# AutoPBT.net
KiCad netlist of a schematic drawn in EAGLE
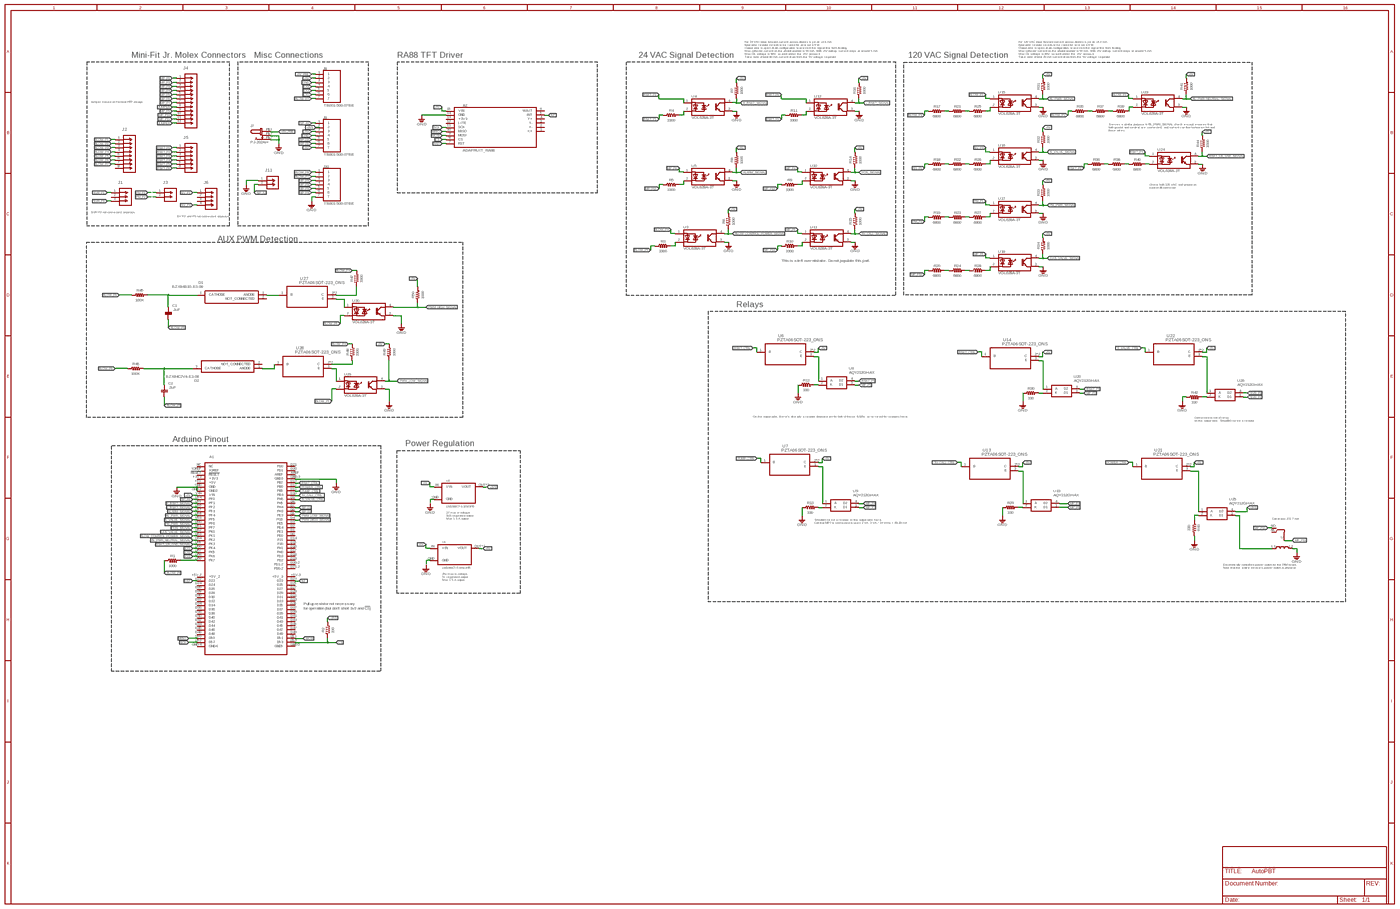
[diagram p0: schematic, sheet 1, overview]
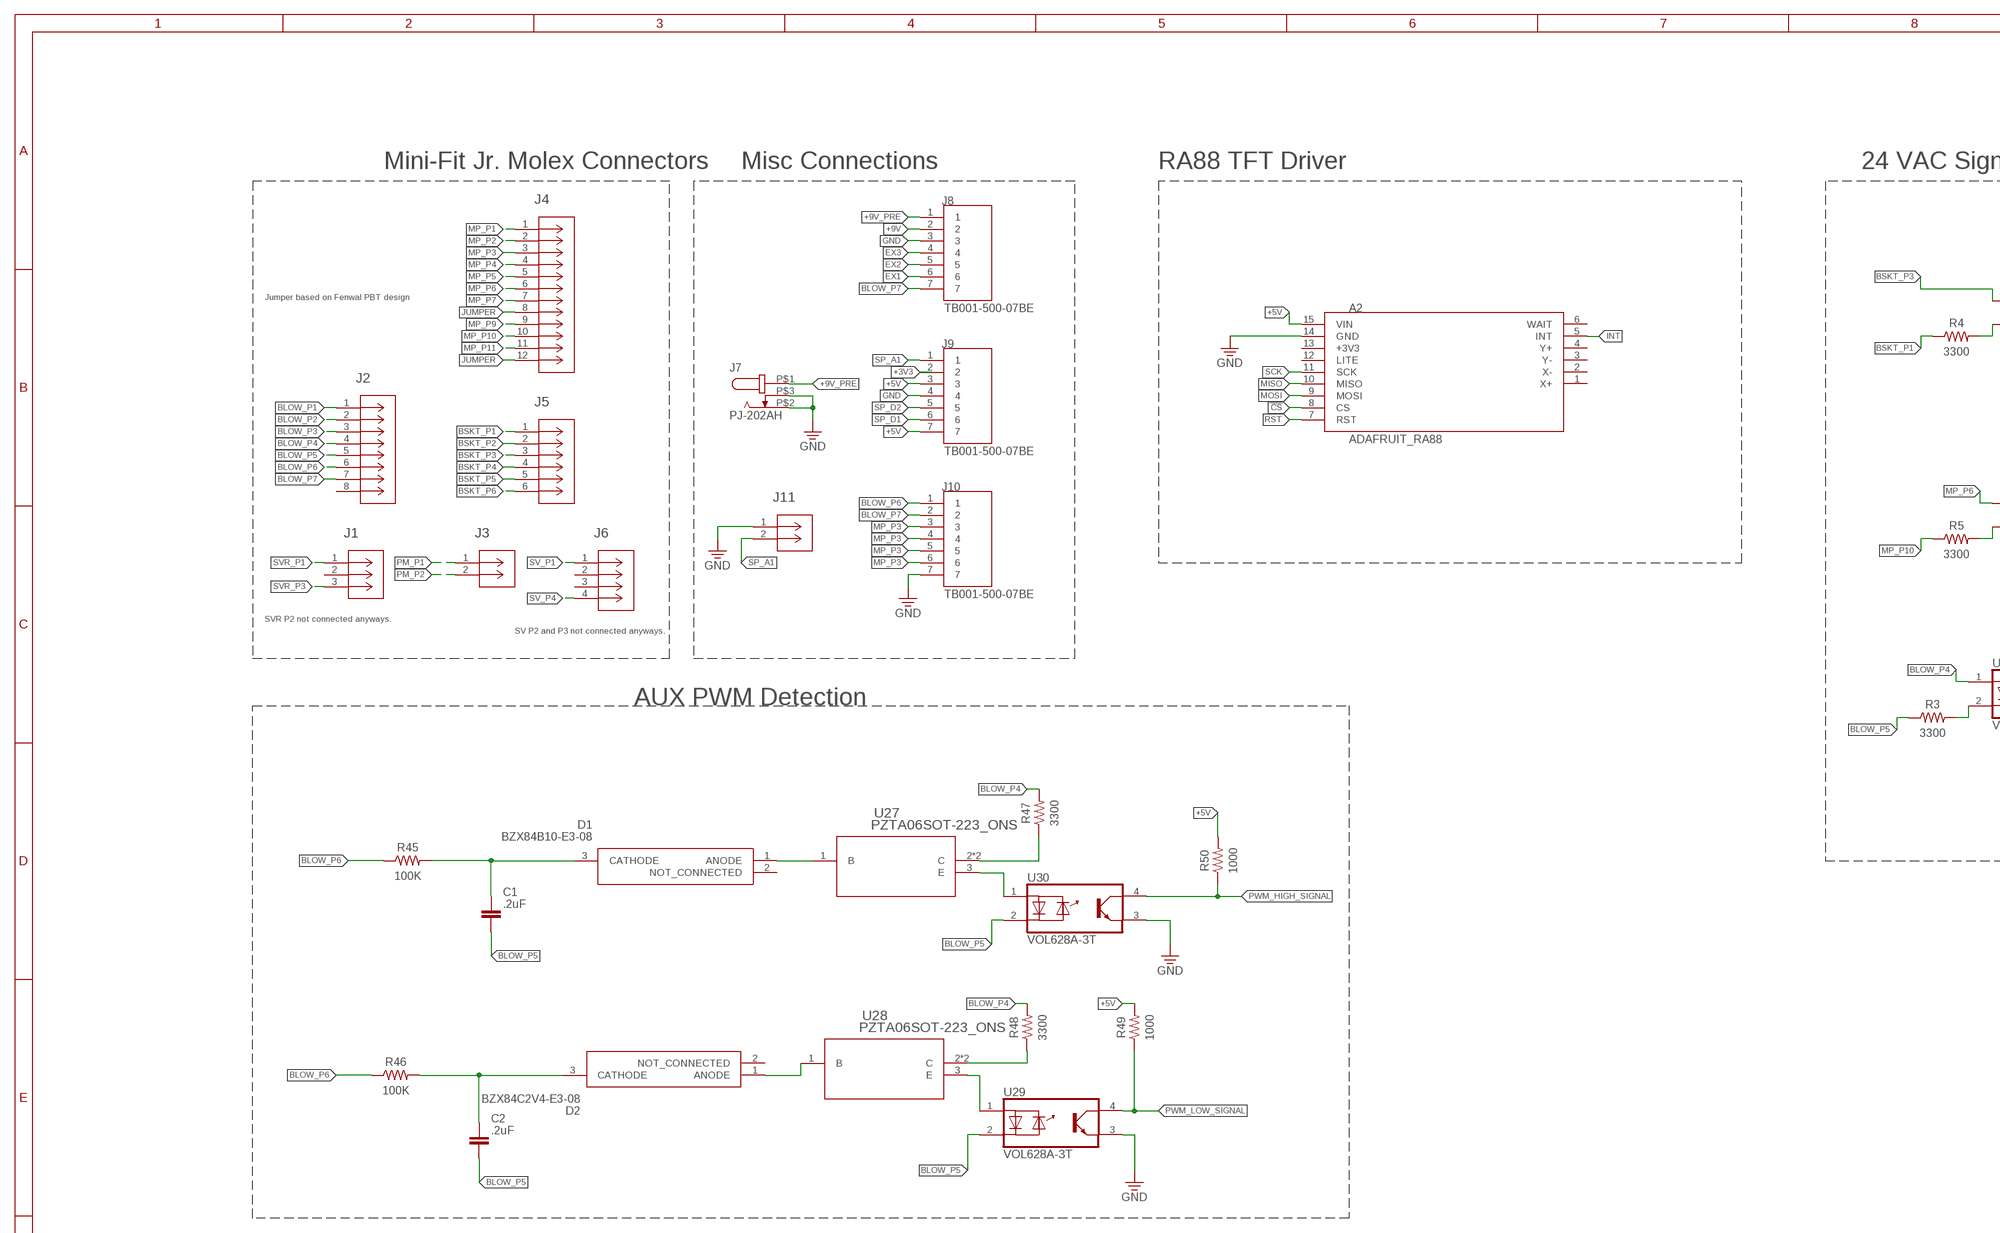
[diagram p1: schematic, sheet 1, part 1 of 4]
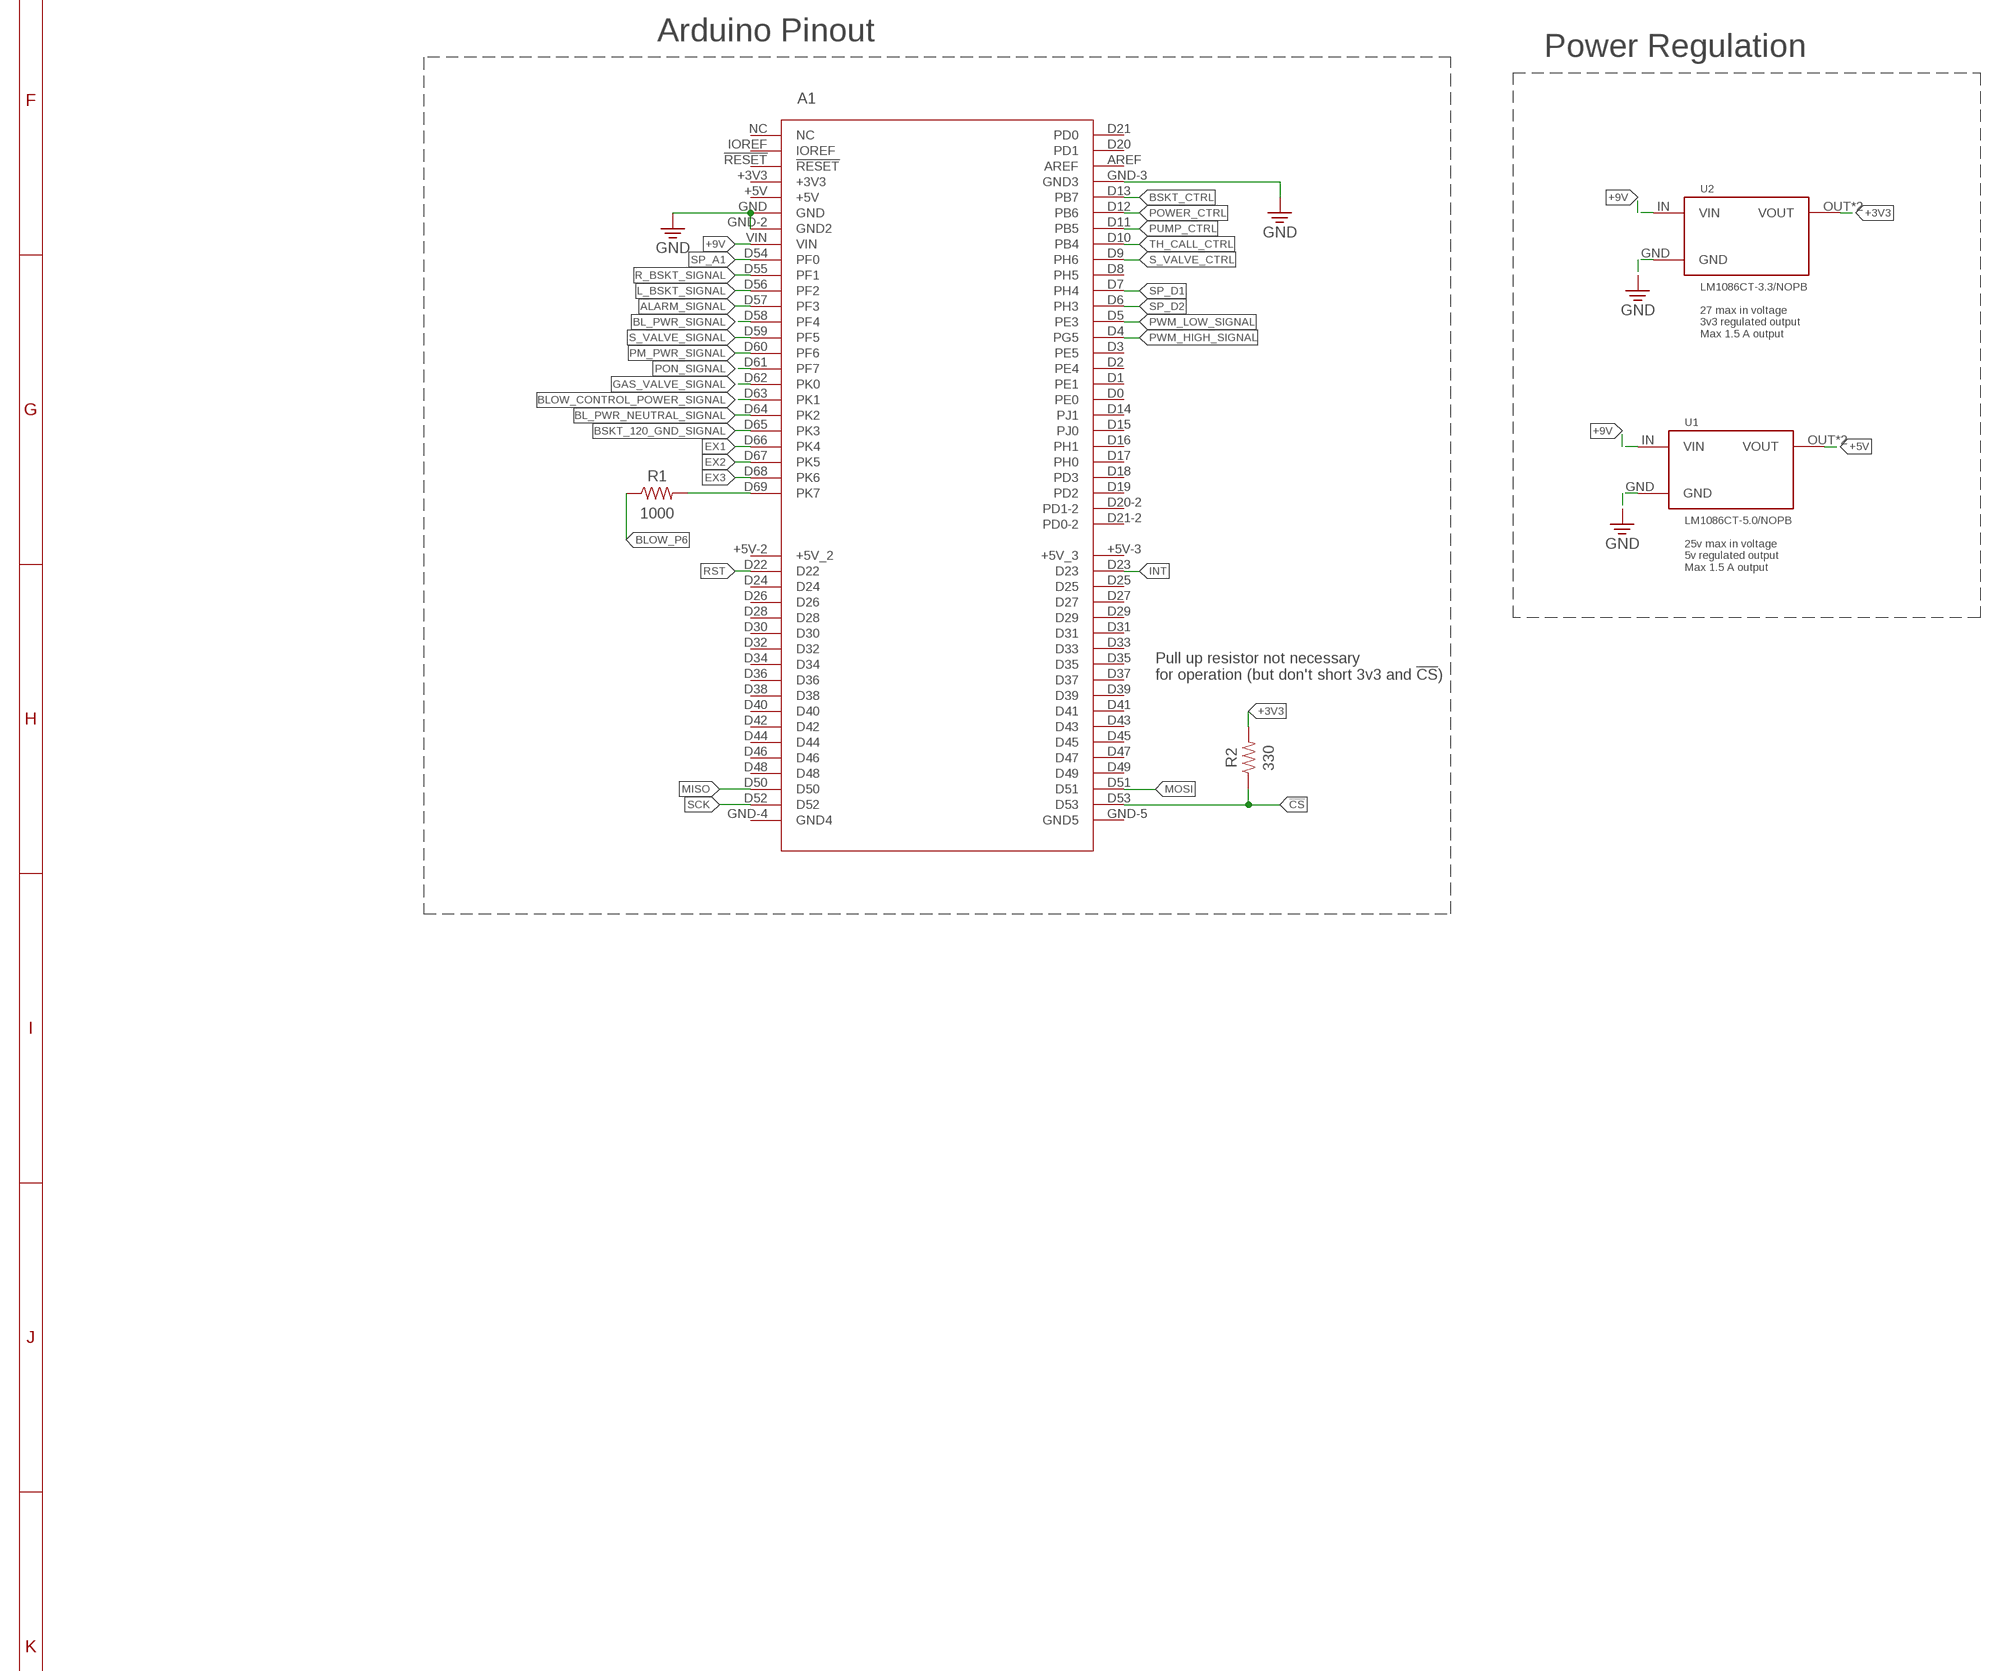
[diagram p2: schematic, sheet 1, part 2 of 4]
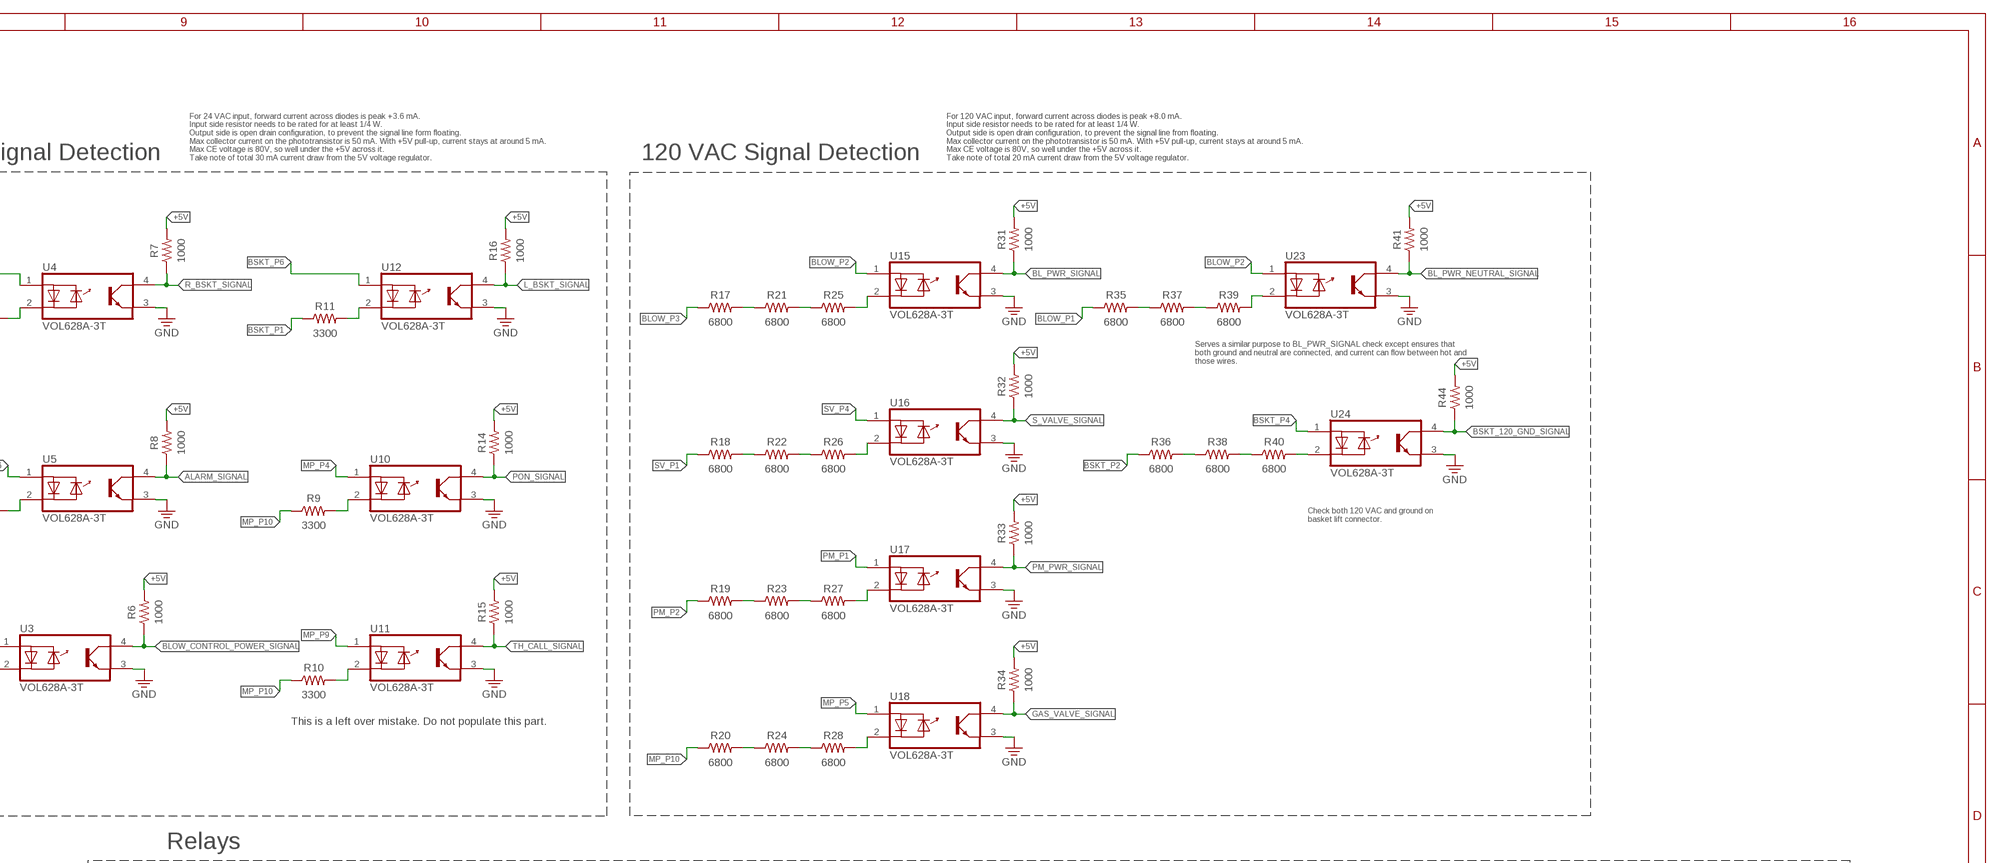
[diagram p3: schematic, sheet 1, part 3 of 4]
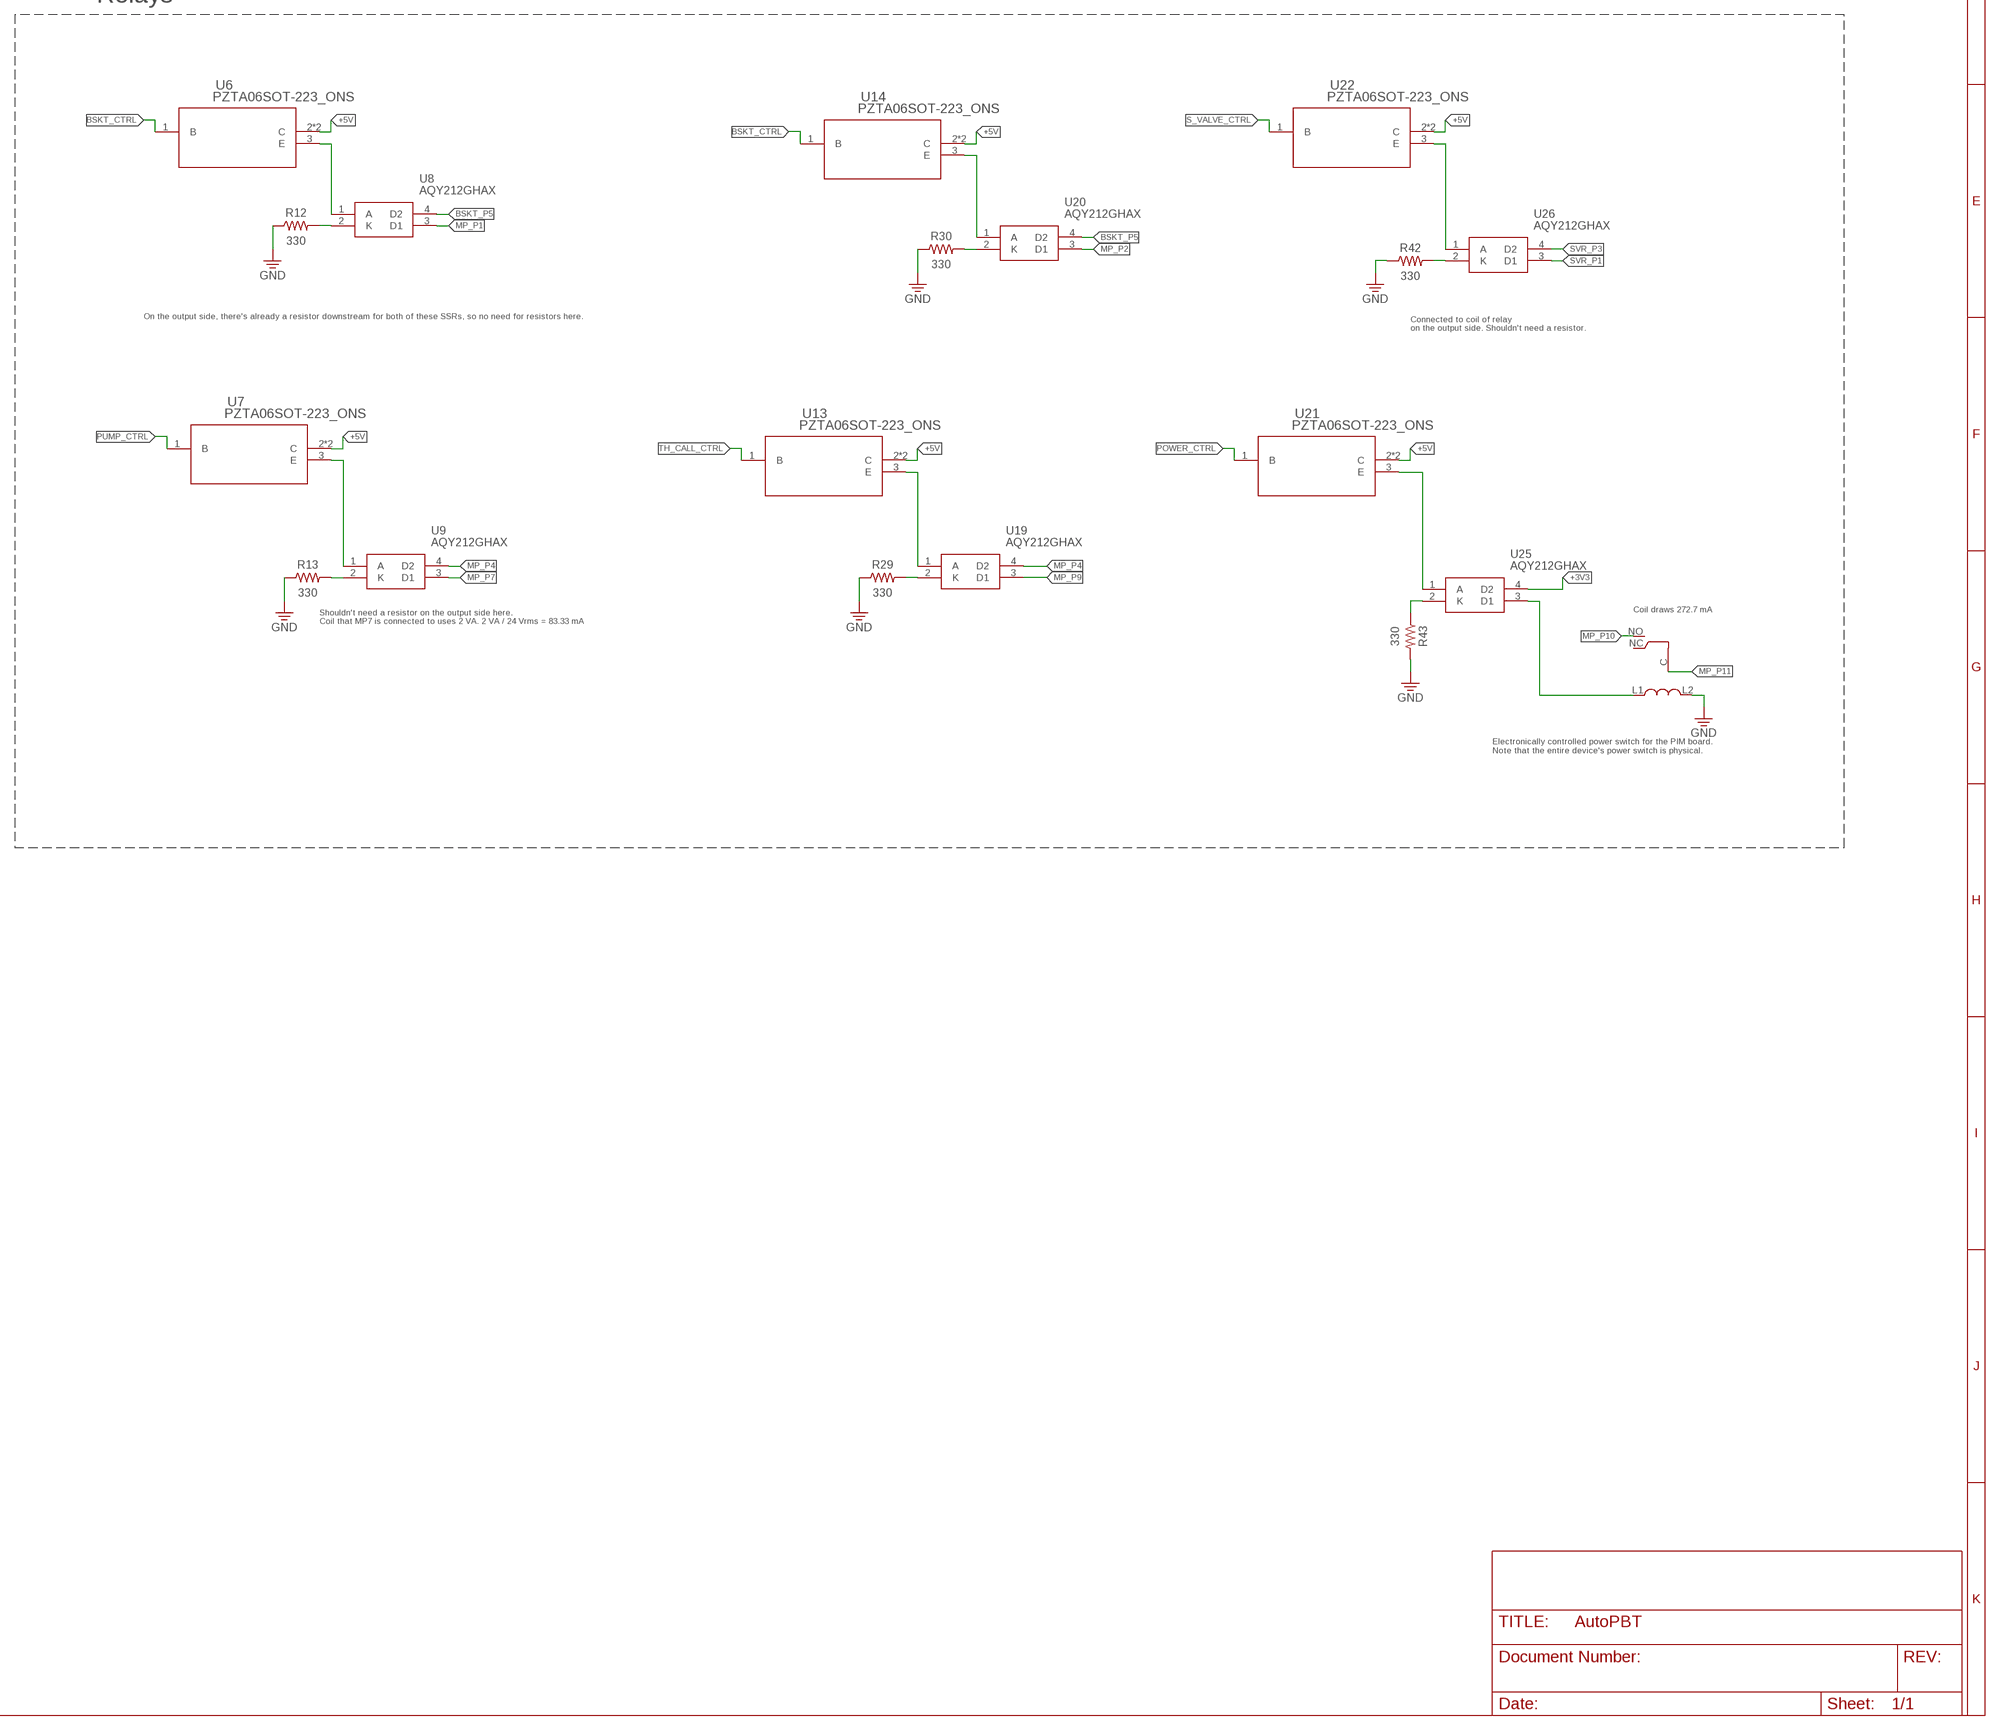
[diagram p4: schematic, sheet 1, part 4 of 4]

(export (version "E")
  (design (tool "Eeschema 10.0.6"))
  (components
    (comp (ref "A1")
      (value "ARDUINO2560ARDUINO2560ACTUAL")
      (footprint "eagle-import:ARDUINO2560PINS")
      (libsource (lib "eagle-import") (part "ARDUINO2560ARDUINO2560ACTUAL"))
    )
    (comp (ref "A2")
      (value "ADAFRUIT_RA88")
      (footprint "eagle-import:RA88")
      (libsource (lib "eagle-import") (part "ADAFRUIT_RA88"))
    )
    (comp (ref "C1")
      (value ".2uF")
      (footprint "eagle-import:CAPC1608X85")
      (libsource (lib "eagle-import") (part "CCHIP-0603(1608-METRIC)_"))
    )
    (comp (ref "C2")
      (value ".2uF")
      (footprint "eagle-import:CAPC1608X85")
      (libsource (lib "eagle-import") (part "CCHIP-0603(1608-METRIC)_"))
    )
    (comp (ref "D1")
      (value "BZX84B10-E3-08")
      (footprint "eagle-import:SOT95P248X115-3N")
      (libsource (lib "eagle-import") (part "BZX84B10-E3-08"))
    )
    (comp (ref "D2")
      (value "BZX84C2V4-E3-08")
      (footprint "eagle-import:SOT95P248X115-3N")
      (fields (field (name "MOUSER_PART_NUMBER") "78-BZX84C2V4-E3-08"))
      (libsource (lib "eagle-import") (part "BZX84C2V4-E3-08"))
    )
    (comp (ref "J1")
      (value "39301039CON_39301039")
      (footprint "eagle-import:CON_39301039")
      (fields
        (field (name "MANUFACTURER_PART_NUMBER") "39301039")
        (field (name "COPYRIGHT") "Copyright (C) 2022 Ultra Librarian. All rights reserved.")
      )
      (libsource (lib "eagle-import") (part "39301039CON_39301039"))
    )
    (comp (ref "J2")
      (value "39281083CON_39281083")
      (footprint "eagle-import:CON_39281083")
      (fields
        (field (name "MANUFACTURER_PART_NUMBER") "39281083")
        (field (name "COPYRIGHT") "Copyright (C) 2022 Ultra Librarian. All rights reserved.")
      )
      (libsource (lib "eagle-import") (part "39281083CON_39281083"))
    )
    (comp (ref "J3")
      (value "39281023CON_39281023")
      (footprint "eagle-import:CON_39281023")
      (fields
        (field (name "MANUFACTURER_PART_NUMBER") "39281023")
        (field (name "COPYRIGHT") "Copyright (C) 2022 Ultra Librarian. All rights reserved.")
      )
      (libsource (lib "eagle-import") (part "39281023CON_39281023"))
    )
    (comp (ref "J4")
      (value "39281123CON_39281123")
      (footprint "eagle-import:CON_39281123")
      (fields
        (field (name "MANUFACTURER_PART_NUMBER") "39281123")
        (field (name "COPYRIGHT") "Copyright (C) 2022 Ultra Librarian. All rights reserved.")
      )
      (libsource (lib "eagle-import") (part "39281123CON_39281123"))
    )
    (comp (ref "J5")
      (value "39281063CON_39281063")
      (footprint "eagle-import:CON_39281063")
      (fields
        (field (name "MANUFACTURER_PART_NUMBER") "39281063")
        (field (name "COPYRIGHT") "Copyright (C) 2022 Ultra Librarian. All rights reserved.")
      )
      (libsource (lib "eagle-import") (part "39281063CON_39281063"))
    )
    (comp (ref "J6")
      (value "39299046CON_39299046")
      (footprint "eagle-import:CON_39299046")
      (fields
        (field (name "MANUFACTURER_PART_NUMBER") "39299046")
        (field (name "COPYRIGHT") "Copyright (C) 2022 Ultra Librarian. All rights reserved.")
      )
      (libsource (lib "eagle-import") (part "39299046CON_39299046"))
    )
    (comp (ref "J7")
      (value "PJ-202AH")
      (footprint "eagle-import:CUI_PJ-202AH")
      (fields (field (name "MANUFACTURER") "CUI INC"))
      (libsource (lib "eagle-import") (part "PJ-202AH"))
    )
    (comp (ref "J8")
      (value "TB001-500-07BE")
      (footprint "eagle-import:CUI_TB001-500-07BE")
      (fields (field (name "MANUFACTURER") "CUI"))
      (libsource (lib "eagle-import") (part "TB001-500-07BE"))
    )
    (comp (ref "J9")
      (value "TB001-500-07BE")
      (footprint "eagle-import:CUI_TB001-500-07BE")
      (fields (field (name "MANUFACTURER") "CUI"))
      (libsource (lib "eagle-import") (part "TB001-500-07BE"))
    )
    (comp (ref "J10")
      (value "TB001-500-07BE")
      (footprint "eagle-import:CUI_TB001-500-07BE")
      (fields (field (name "MANUFACTURER") "CUI"))
      (libsource (lib "eagle-import") (part "TB001-500-07BE"))
    )
    (comp (ref "J11")
      (value "430450212CON_430450212_MOL")
      (footprint "eagle-import:CON_430450212_MOL")
      (fields
        (field (name "MANUFACTURER_PART_NUMBER") "430450212")
        (field (name "COPYRIGHT") "Copyright (C) 2022 Ultra Librarian. All rights reserved.")
      )
      (libsource (lib "eagle-import") (part "430450212CON_430450212_MOL"))
    )
    (comp (ref "K1")
      (value "J107F1CS203VDC.80")
      (footprint "eagle-import:J107F1CS203VDC.80")
      (libsource (lib "eagle-import") (part "J107F1CS203VDC.80"))
    )
    (comp (ref "R1")
      (value "1000")
      (footprint "eagle-import:RESC1608X60")
      (libsource (lib "eagle-import") (part "R-USCHIP-0603(1608-METRIC)_"))
    )
    (comp (ref "R2")
      (value "330")
      (footprint "eagle-import:RESC1608X60")
      (libsource (lib "eagle-import") (part "R-USCHIP-0603(1608-METRIC)_"))
    )
    (comp (ref "R3")
      (value "3300")
      (footprint "eagle-import:RESC1608X60")
      (libsource (lib "eagle-import") (part "R-USCHIP-0603(1608-METRIC)_"))
    )
    (comp (ref "R4")
      (value "3300")
      (footprint "eagle-import:RESC1608X60")
      (libsource (lib "eagle-import") (part "R-USCHIP-0603(1608-METRIC)_"))
    )
    (comp (ref "R5")
      (value "3300")
      (footprint "eagle-import:RESC1608X60")
      (libsource (lib "eagle-import") (part "R-USCHIP-0603(1608-METRIC)_"))
    )
    (comp (ref "R6")
      (value "1000")
      (footprint "eagle-import:RESC1608X60")
      (libsource (lib "eagle-import") (part "R-USCHIP-0603(1608-METRIC)_"))
    )
    (comp (ref "R7")
      (value "1000")
      (footprint "eagle-import:RESC1608X60")
      (libsource (lib "eagle-import") (part "R-USCHIP-0603(1608-METRIC)_"))
    )
    (comp (ref "R8")
      (value "1000")
      (footprint "eagle-import:RESC1608X60")
      (libsource (lib "eagle-import") (part "R-USCHIP-0603(1608-METRIC)_"))
    )
    (comp (ref "R9")
      (value "3300")
      (footprint "eagle-import:RESC1608X60")
      (libsource (lib "eagle-import") (part "R-USCHIP-0603(1608-METRIC)_"))
    )
    (comp (ref "R10")
      (value "3300")
      (footprint "eagle-import:RESC1608X60")
      (libsource (lib "eagle-import") (part "R-USCHIP-0603(1608-METRIC)_"))
    )
    (comp (ref "R11")
      (value "3300")
      (footprint "eagle-import:RESC1608X60")
      (libsource (lib "eagle-import") (part "R-USCHIP-0603(1608-METRIC)_"))
    )
    (comp (ref "R12")
      (value "330")
      (footprint "eagle-import:RESC1608X60")
      (libsource (lib "eagle-import") (part "R-USCHIP-0603(1608-METRIC)_"))
    )
    (comp (ref "R13")
      (value "330")
      (footprint "eagle-import:RESC1608X60")
      (libsource (lib "eagle-import") (part "R-USCHIP-0603(1608-METRIC)_"))
    )
    (comp (ref "R14")
      (value "1000")
      (footprint "eagle-import:RESC1608X60")
      (libsource (lib "eagle-import") (part "R-USCHIP-0603(1608-METRIC)_"))
    )
    (comp (ref "R15")
      (value "1000")
      (footprint "eagle-import:RESC1608X60")
      (libsource (lib "eagle-import") (part "R-USCHIP-0603(1608-METRIC)_"))
    )
    (comp (ref "R16")
      (value "1000")
      (footprint "eagle-import:RESC1608X60")
      (libsource (lib "eagle-import") (part "R-USCHIP-0603(1608-METRIC)_"))
    )
    (comp (ref "R17")
      (value "6800")
      (footprint "eagle-import:RESC1608X60")
      (libsource (lib "eagle-import") (part "R-USCHIP-0603(1608-METRIC)_"))
    )
    (comp (ref "R18")
      (value "6800")
      (footprint "eagle-import:RESC1608X60")
      (libsource (lib "eagle-import") (part "R-USCHIP-0603(1608-METRIC)_"))
    )
    (comp (ref "R19")
      (value "6800")
      (footprint "eagle-import:RESC1608X60")
      (libsource (lib "eagle-import") (part "R-USCHIP-0603(1608-METRIC)_"))
    )
    (comp (ref "R20")
      (value "6800")
      (footprint "eagle-import:RESC1608X60")
      (libsource (lib "eagle-import") (part "R-USCHIP-0603(1608-METRIC)_"))
    )
    (comp (ref "R21")
      (value "6800")
      (footprint "eagle-import:RESC1608X60")
      (libsource (lib "eagle-import") (part "R-USCHIP-0603(1608-METRIC)_"))
    )
    (comp (ref "R22")
      (value "6800")
      (footprint "eagle-import:RESC1608X60")
      (libsource (lib "eagle-import") (part "R-USCHIP-0603(1608-METRIC)_"))
    )
    (comp (ref "R23")
      (value "6800")
      (footprint "eagle-import:RESC1608X60")
      (libsource (lib "eagle-import") (part "R-USCHIP-0603(1608-METRIC)_"))
    )
    (comp (ref "R24")
      (value "6800")
      (footprint "eagle-import:RESC1608X60")
      (libsource (lib "eagle-import") (part "R-USCHIP-0603(1608-METRIC)_"))
    )
    (comp (ref "R25")
      (value "6800")
      (footprint "eagle-import:RESC1608X60")
      (libsource (lib "eagle-import") (part "R-USCHIP-0603(1608-METRIC)_"))
    )
    (comp (ref "R26")
      (value "6800")
      (footprint "eagle-import:RESC1608X60")
      (libsource (lib "eagle-import") (part "R-USCHIP-0603(1608-METRIC)_"))
    )
    (comp (ref "R27")
      (value "6800")
      (footprint "eagle-import:RESC1608X60")
      (libsource (lib "eagle-import") (part "R-USCHIP-0603(1608-METRIC)_"))
    )
    (comp (ref "R28")
      (value "6800")
      (footprint "eagle-import:RESC1608X60")
      (libsource (lib "eagle-import") (part "R-USCHIP-0603(1608-METRIC)_"))
    )
    (comp (ref "R29")
      (value "330")
      (footprint "eagle-import:RESC1608X60")
      (libsource (lib "eagle-import") (part "R-USCHIP-0603(1608-METRIC)_"))
    )
    (comp (ref "R30")
      (value "330")
      (footprint "eagle-import:RESC1608X60")
      (libsource (lib "eagle-import") (part "R-USCHIP-0603(1608-METRIC)_"))
    )
    (comp (ref "R31")
      (value "1000")
      (footprint "eagle-import:RESC1608X60")
      (libsource (lib "eagle-import") (part "R-USCHIP-0603(1608-METRIC)_"))
    )
    (comp (ref "R32")
      (value "1000")
      (footprint "eagle-import:RESC1608X60")
      (libsource (lib "eagle-import") (part "R-USCHIP-0603(1608-METRIC)_"))
    )
    (comp (ref "R33")
      (value "1000")
      (footprint "eagle-import:RESC1608X60")
      (libsource (lib "eagle-import") (part "R-USCHIP-0603(1608-METRIC)_"))
    )
    (comp (ref "R34")
      (value "1000")
      (footprint "eagle-import:RESC1608X60")
      (libsource (lib "eagle-import") (part "R-USCHIP-0603(1608-METRIC)_"))
    )
    (comp (ref "R35")
      (value "6800")
      (footprint "eagle-import:RESC1608X60")
      (libsource (lib "eagle-import") (part "R-USCHIP-0603(1608-METRIC)_"))
    )
    (comp (ref "R36")
      (value "6800")
      (footprint "eagle-import:RESC1608X60")
      (libsource (lib "eagle-import") (part "R-USCHIP-0603(1608-METRIC)_"))
    )
    (comp (ref "R37")
      (value "6800")
      (footprint "eagle-import:RESC1608X60")
      (libsource (lib "eagle-import") (part "R-USCHIP-0603(1608-METRIC)_"))
    )
    (comp (ref "R38")
      (value "6800")
      (footprint "eagle-import:RESC1608X60")
      (libsource (lib "eagle-import") (part "R-USCHIP-0603(1608-METRIC)_"))
    )
    (comp (ref "R39")
      (value "6800")
      (footprint "eagle-import:RESC1608X60")
      (libsource (lib "eagle-import") (part "R-USCHIP-0603(1608-METRIC)_"))
    )
    (comp (ref "R40")
      (value "6800")
      (footprint "eagle-import:RESC1608X60")
      (libsource (lib "eagle-import") (part "R-USCHIP-0603(1608-METRIC)_"))
    )
    (comp (ref "R41")
      (value "1000")
      (footprint "eagle-import:RESC1608X60")
      (libsource (lib "eagle-import") (part "R-USCHIP-0603(1608-METRIC)_"))
    )
    (comp (ref "R42")
      (value "330")
      (footprint "eagle-import:RESC1608X60")
      (libsource (lib "eagle-import") (part "R-USCHIP-0603(1608-METRIC)_"))
    )
    (comp (ref "R43")
      (value "330")
      (footprint "eagle-import:RESC1608X60")
      (libsource (lib "eagle-import") (part "R-USCHIP-0603(1608-METRIC)_"))
    )
    (comp (ref "R44")
      (value "1000")
      (footprint "eagle-import:RESC1608X60")
      (libsource (lib "eagle-import") (part "R-USCHIP-0603(1608-METRIC)_"))
    )
    (comp (ref "R45")
      (value "100K")
      (footprint "eagle-import:RESC1608X60")
      (libsource (lib "eagle-import") (part "R-USCHIP-0603(1608-METRIC)_"))
    )
    (comp (ref "R46")
      (value "100K")
      (footprint "eagle-import:RESC1608X60")
      (libsource (lib "eagle-import") (part "R-USCHIP-0603(1608-METRIC)_"))
    )
    (comp (ref "R47")
      (value "3300")
      (footprint "eagle-import:RESC1608X60")
      (libsource (lib "eagle-import") (part "R-USCHIP-0603(1608-METRIC)_"))
    )
    (comp (ref "R48")
      (value "3300")
      (footprint "eagle-import:RESC1608X60")
      (libsource (lib "eagle-import") (part "R-USCHIP-0603(1608-METRIC)_"))
    )
    (comp (ref "R49")
      (value "1000")
      (footprint "eagle-import:RESC1608X60")
      (libsource (lib "eagle-import") (part "R-USCHIP-0603(1608-METRIC)_"))
    )
    (comp (ref "R50")
      (value "1000")
      (footprint "eagle-import:RESC1608X60")
      (libsource (lib "eagle-import") (part "R-USCHIP-0603(1608-METRIC)_"))
    )
    (comp (ref "U1")
      (value "LM1086CT-5.0/NOPB")
      (footprint "eagle-import:LM1086CT-3.3_NOPB")
      (libsource (lib "eagle-import") (part "LM1086CT-5.0/NOPB"))
    )
    (comp (ref "U2")
      (value "LM1086CT-3.3/NOPB")
      (footprint "eagle-import:LM1086CT-3.3_NOPB")
      (libsource (lib "eagle-import") (part "LM1086CT-3.3/NOPB"))
    )
    (comp (ref "U3")
      (value "VOL628A-3T")
      (footprint "eagle-import:SOIC254P1020X230-4N")
      (fields (field (name "MANUFACTURER") "VISHAY"))
      (libsource (lib "eagle-import") (part "VOL628A-3T"))
    )
    (comp (ref "U4")
      (value "VOL628A-3T")
      (footprint "eagle-import:SOIC254P1020X230-4N")
      (fields (field (name "MANUFACTURER") "VISHAY"))
      (libsource (lib "eagle-import") (part "VOL628A-3T"))
    )
    (comp (ref "U5")
      (value "VOL628A-3T")
      (footprint "eagle-import:SOIC254P1020X230-4N")
      (fields (field (name "MANUFACTURER") "VISHAY"))
      (libsource (lib "eagle-import") (part "VOL628A-3T"))
    )
    (comp (ref "U6")
      (value "PZTA06SOT-223_ONS")
      (footprint "eagle-import:SOT-223_ONS")
      (fields
        (field (name "MANUFACTURER_PART_NUMBER") "PZTA06")
        (field (name "COPYRIGHT") "Copyright (C) 2022 Ultra Librarian. All rights reserved.")
      )
      (libsource (lib "eagle-import") (part "PZTA06SOT-223_ONS"))
    )
    (comp (ref "U7")
      (value "PZTA06SOT-223_ONS")
      (footprint "eagle-import:SOT-223_ONS")
      (fields
        (field (name "MANUFACTURER_PART_NUMBER") "PZTA06")
        (field (name "COPYRIGHT") "Copyright (C) 2022 Ultra Librarian. All rights reserved.")
      )
      (libsource (lib "eagle-import") (part "PZTA06SOT-223_ONS"))
    )
    (comp (ref "U8")
      (value "AQY212GHAX")
      (footprint "eagle-import:SOP254P962X315-4N")
      (fields (field (name "MOUSER_PART_NUMBER") "667-AQY212GHAX"))
      (libsource (lib "eagle-import") (part "AQY212GHAX"))
    )
    (comp (ref "U9")
      (value "AQY212GHAX")
      (footprint "eagle-import:SOP254P962X315-4N")
      (fields (field (name "MOUSER_PART_NUMBER") "667-AQY212GHAX"))
      (libsource (lib "eagle-import") (part "AQY212GHAX"))
    )
    (comp (ref "U10")
      (value "VOL628A-3T")
      (footprint "eagle-import:SOIC254P1020X230-4N")
      (fields (field (name "MANUFACTURER") "VISHAY"))
      (libsource (lib "eagle-import") (part "VOL628A-3T"))
    )
    (comp (ref "U11")
      (value "VOL628A-3T")
      (footprint "eagle-import:SOIC254P1020X230-4N")
      (fields (field (name "MANUFACTURER") "VISHAY"))
      (libsource (lib "eagle-import") (part "VOL628A-3T"))
    )
    (comp (ref "U12")
      (value "VOL628A-3T")
      (footprint "eagle-import:SOIC254P1020X230-4N")
      (fields (field (name "MANUFACTURER") "VISHAY"))
      (libsource (lib "eagle-import") (part "VOL628A-3T"))
    )
    (comp (ref "U13")
      (value "PZTA06SOT-223_ONS")
      (footprint "eagle-import:SOT-223_ONS")
      (fields
        (field (name "MANUFACTURER_PART_NUMBER") "PZTA06")
        (field (name "COPYRIGHT") "Copyright (C) 2022 Ultra Librarian. All rights reserved.")
      )
      (libsource (lib "eagle-import") (part "PZTA06SOT-223_ONS"))
    )
    (comp (ref "U14")
      (value "PZTA06SOT-223_ONS")
      (footprint "eagle-import:SOT-223_ONS")
      (fields
        (field (name "MANUFACTURER_PART_NUMBER") "PZTA06")
        (field (name "COPYRIGHT") "Copyright (C) 2022 Ultra Librarian. All rights reserved.")
      )
      (libsource (lib "eagle-import") (part "PZTA06SOT-223_ONS"))
    )
    (comp (ref "U15")
      (value "VOL628A-3T")
      (footprint "eagle-import:SOIC254P1020X230-4N")
      (fields (field (name "MANUFACTURER") "VISHAY"))
      (libsource (lib "eagle-import") (part "VOL628A-3T"))
    )
    (comp (ref "U16")
      (value "VOL628A-3T")
      (footprint "eagle-import:SOIC254P1020X230-4N")
      (fields (field (name "MANUFACTURER") "VISHAY"))
      (libsource (lib "eagle-import") (part "VOL628A-3T"))
    )
    (comp (ref "U17")
      (value "VOL628A-3T")
      (footprint "eagle-import:SOIC254P1020X230-4N")
      (fields (field (name "MANUFACTURER") "VISHAY"))
      (libsource (lib "eagle-import") (part "VOL628A-3T"))
    )
    (comp (ref "U18")
      (value "VOL628A-3T")
      (footprint "eagle-import:SOIC254P1020X230-4N")
      (fields (field (name "MANUFACTURER") "VISHAY"))
      (libsource (lib "eagle-import") (part "VOL628A-3T"))
    )
    (comp (ref "U19")
      (value "AQY212GHAX")
      (footprint "eagle-import:SOP254P962X315-4N")
      (fields (field (name "MOUSER_PART_NUMBER") "667-AQY212GHAX"))
      (libsource (lib "eagle-import") (part "AQY212GHAX"))
    )
    (comp (ref "U20")
      (value "AQY212GHAX")
      (footprint "eagle-import:SOP254P962X315-4N")
      (fields (field (name "MOUSER_PART_NUMBER") "667-AQY212GHAX"))
      (libsource (lib "eagle-import") (part "AQY212GHAX"))
    )
    (comp (ref "U21")
      (value "PZTA06SOT-223_ONS")
      (footprint "eagle-import:SOT-223_ONS")
      (fields
        (field (name "MANUFACTURER_PART_NUMBER") "PZTA06")
        (field (name "COPYRIGHT") "Copyright (C) 2022 Ultra Librarian. All rights reserved.")
      )
      (libsource (lib "eagle-import") (part "PZTA06SOT-223_ONS"))
    )
    (comp (ref "U22")
      (value "PZTA06SOT-223_ONS")
      (footprint "eagle-import:SOT-223_ONS")
      (fields
        (field (name "MANUFACTURER_PART_NUMBER") "PZTA06")
        (field (name "COPYRIGHT") "Copyright (C) 2022 Ultra Librarian. All rights reserved.")
      )
      (libsource (lib "eagle-import") (part "PZTA06SOT-223_ONS"))
    )
    (comp (ref "U23")
      (value "VOL628A-3T")
      (footprint "eagle-import:SOIC254P1020X230-4N")
      (fields (field (name "MANUFACTURER") "VISHAY"))
      (libsource (lib "eagle-import") (part "VOL628A-3T"))
    )
    (comp (ref "U24")
      (value "VOL628A-3T")
      (footprint "eagle-import:SOIC254P1020X230-4N")
      (fields (field (name "MANUFACTURER") "VISHAY"))
      (libsource (lib "eagle-import") (part "VOL628A-3T"))
    )
    (comp (ref "U25")
      (value "AQY212GHAX")
      (footprint "eagle-import:SOP254P962X315-4N")
      (fields (field (name "MOUSER_PART_NUMBER") "667-AQY212GHAX"))
      (libsource (lib "eagle-import") (part "AQY212GHAX"))
    )
    (comp (ref "U26")
      (value "AQY212GHAX")
      (footprint "eagle-import:SOP254P962X315-4N")
      (fields (field (name "MOUSER_PART_NUMBER") "667-AQY212GHAX"))
      (libsource (lib "eagle-import") (part "AQY212GHAX"))
    )
    (comp (ref "U27")
      (value "PZTA06SOT-223_ONS")
      (footprint "eagle-import:SOT-223_ONS")
      (fields
        (field (name "MANUFACTURER_PART_NUMBER") "PZTA06")
        (field (name "COPYRIGHT") "Copyright (C) 2022 Ultra Librarian. All rights reserved.")
      )
      (libsource (lib "eagle-import") (part "PZTA06SOT-223_ONS"))
    )
    (comp (ref "U28")
      (value "PZTA06SOT-223_ONS")
      (footprint "eagle-import:SOT-223_ONS")
      (fields
        (field (name "MANUFACTURER_PART_NUMBER") "PZTA06")
        (field (name "COPYRIGHT") "Copyright (C) 2022 Ultra Librarian. All rights reserved.")
      )
      (libsource (lib "eagle-import") (part "PZTA06SOT-223_ONS"))
    )
    (comp (ref "U29")
      (value "VOL628A-3T")
      (footprint "eagle-import:SOIC254P1020X230-4N")
      (fields (field (name "MANUFACTURER") "VISHAY"))
      (libsource (lib "eagle-import") (part "VOL628A-3T"))
    )
    (comp (ref "U30")
      (value "VOL628A-3T")
      (footprint "eagle-import:SOIC254P1020X230-4N")
      (fields (field (name "MANUFACTURER") "VISHAY"))
      (libsource (lib "eagle-import") (part "VOL628A-3T"))
    )
  )
  (nets
    (net (code "1") (name "+3V3") (class "Default")
      (node (ref "J9") (pin "2") (pinfunction "2_2") (pintype "passive"))
      (node (ref "R2") (pin "2") (pinfunction "2_2") (pintype "passive"))
      (node (ref "U2") (pin "OUT") (pinfunction "VOUT_OUT") (pintype "bidirectional"))
      (node (ref "U2") (pin "OUT2") (pinfunction "VOUT_OUT2") (pintype "bidirectional"))
      (node (ref "U25") (pin "4") (pinfunction "D2_4") (pintype "bidirectional"))
    )
    (net (code "2") (name "+5V") (class "Default")
      (node (ref "A2") (pin "15") (pinfunction "VIN_15") (pintype "bidirectional"))
      (node (ref "J9") (pin "3") (pinfunction "3_3") (pintype "passive"))
      (node (ref "J9") (pin "7") (pinfunction "7_7") (pintype "passive"))
      (node (ref "R14") (pin "2") (pinfunction "2_2") (pintype "passive"))
      (node (ref "R15") (pin "2") (pinfunction "2_2") (pintype "passive"))
      (node (ref "R16") (pin "2") (pinfunction "2_2") (pintype "passive"))
      (node (ref "R31") (pin "2") (pinfunction "2_2") (pintype "passive"))
      (node (ref "R32") (pin "2") (pinfunction "2_2") (pintype "passive"))
      (node (ref "R33") (pin "2") (pinfunction "2_2") (pintype "passive"))
      (node (ref "R34") (pin "2") (pinfunction "2_2") (pintype "passive"))
      (node (ref "R41") (pin "2") (pinfunction "2_2") (pintype "passive"))
      (node (ref "R44") (pin "2") (pinfunction "2_2") (pintype "passive"))
      (node (ref "R49") (pin "2") (pinfunction "2_2") (pintype "passive"))
      (node (ref "R50") (pin "2") (pinfunction "2_2") (pintype "passive"))
      (node (ref "R6") (pin "2") (pinfunction "2_2") (pintype "passive"))
      (node (ref "R7") (pin "2") (pinfunction "2_2") (pintype "passive"))
      (node (ref "R8") (pin "2") (pinfunction "2_2") (pintype "passive"))
      (node (ref "U1") (pin "OUT") (pinfunction "VOUT_OUT") (pintype "bidirectional"))
      (node (ref "U1") (pin "OUT2") (pinfunction "VOUT_OUT2") (pintype "bidirectional"))
      (node (ref "U13") (pin "2") (pinfunction "C_2") (pintype "passive"))
      (node (ref "U13") (pin "4") (pinfunction "C_4") (pintype "passive"))
      (node (ref "U14") (pin "2") (pinfunction "C_2") (pintype "passive"))
      (node (ref "U14") (pin "4") (pinfunction "C_4") (pintype "passive"))
      (node (ref "U21") (pin "2") (pinfunction "C_2") (pintype "passive"))
      (node (ref "U21") (pin "4") (pinfunction "C_4") (pintype "passive"))
      (node (ref "U22") (pin "2") (pinfunction "C_2") (pintype "passive"))
      (node (ref "U22") (pin "4") (pinfunction "C_4") (pintype "passive"))
      (node (ref "U6") (pin "2") (pinfunction "C_2") (pintype "passive"))
      (node (ref "U6") (pin "4") (pinfunction "C_4") (pintype "passive"))
      (node (ref "U7") (pin "2") (pinfunction "C_2") (pintype "passive"))
      (node (ref "U7") (pin "4") (pinfunction "C_4") (pintype "passive"))
    )
    (net (code "3") (name "+9V") (class "Default")
      (node (ref "A1") (pin "VIN") (pinfunction "VIN_VIN") (pintype "bidirectional"))
      (node (ref "J8") (pin "2") (pinfunction "2_2") (pintype "passive"))
      (node (ref "U1") (pin "IN") (pinfunction "VIN_IN") (pintype "bidirectional"))
      (node (ref "U2") (pin "IN") (pinfunction "VIN_IN") (pintype "bidirectional"))
    )
    (net (code "4") (name "+9V_PRE") (class "Default")
      (node (ref "J7") (pin "P$1") (pinfunction "1_P$1") (pintype "passive"))
      (node (ref "J8") (pin "1") (pinfunction "1_1") (pintype "passive"))
    )
    (net (code "5") (name "/~{CS}") (class "Default")
      (node (ref "A1") (pin "D53") (pinfunction "D53_D53") (pintype "bidirectional"))
      (node (ref "A2") (pin "8") (pinfunction "CS_8") (pintype "bidirectional"))
      (node (ref "R2") (pin "1") (pinfunction "1_1") (pintype "passive"))
    )
    (net (code "6") (name "ALARM_SIGNAL") (class "Default")
      (node (ref "A1") (pin "D57") (pinfunction "PF3_D57") (pintype "bidirectional"))
      (node (ref "R8") (pin "1") (pinfunction "1_1") (pintype "passive"))
      (node (ref "U5") (pin "4") (pinfunction "CO_4") (pintype "passive"))
    )
    (net (code "7") (name "BLOW_CONTROL_POWER_SIGNAL") (class "Default")
      (node (ref "A1") (pin "D63") (pinfunction "PK1_D63") (pintype "bidirectional"))
      (node (ref "R6") (pin "1") (pinfunction "1_1") (pintype "passive"))
      (node (ref "U3") (pin "4") (pinfunction "CO_4") (pintype "passive"))
    )
    (net (code "8") (name "BLOW_P1") (class "Default")
      (node (ref "J2") (pin "1") (pinfunction "1_1") (pintype "passive"))
      (node (ref "R35") (pin "1") (pinfunction "1_1") (pintype "passive"))
    )
    (net (code "9") (name "BLOW_P2") (class "Default")
      (node (ref "J2") (pin "2") (pinfunction "2_2") (pintype "passive"))
      (node (ref "U15") (pin "1") (pinfunction "A/C_1") (pintype "passive"))
      (node (ref "U23") (pin "1") (pinfunction "A/C_1") (pintype "passive"))
    )
    (net (code "10") (name "BLOW_P3") (class "Default")
      (node (ref "J2") (pin "3") (pinfunction "3_3") (pintype "passive"))
      (node (ref "R17") (pin "1") (pinfunction "1_1") (pintype "passive"))
    )
    (net (code "11") (name "BLOW_P4") (class "Default")
      (node (ref "J2") (pin "4") (pinfunction "4_4") (pintype "passive"))
      (node (ref "R47") (pin "2") (pinfunction "2_2") (pintype "passive"))
      (node (ref "R48") (pin "2") (pinfunction "2_2") (pintype "passive"))
      (node (ref "U3") (pin "1") (pinfunction "A/C_1") (pintype "passive"))
    )
    (net (code "12") (name "BLOW_P5") (class "Default")
      (node (ref "C1") (pin "2") (pinfunction "2_2") (pintype "passive"))
      (node (ref "C2") (pin "2") (pinfunction "2_2") (pintype "passive"))
      (node (ref "J2") (pin "5") (pinfunction "5_5") (pintype "passive"))
      (node (ref "R3") (pin "1") (pinfunction "1_1") (pintype "passive"))
      (node (ref "U29") (pin "2") (pinfunction "C/A_2") (pintype "passive"))
      (node (ref "U30") (pin "2") (pinfunction "C/A_2") (pintype "passive"))
    )
    (net (code "13") (name "BLOW_P6") (class "Default")
      (node (ref "J10") (pin "1") (pinfunction "1_1") (pintype "passive"))
      (node (ref "J2") (pin "6") (pinfunction "6_6") (pintype "passive"))
      (node (ref "R1") (pin "1") (pinfunction "1_1") (pintype "passive"))
      (node (ref "R45") (pin "1") (pinfunction "1_1") (pintype "passive"))
      (node (ref "R46") (pin "1") (pinfunction "1_1") (pintype "passive"))
    )
    (net (code "14") (name "BLOW_P7") (class "Default")
      (node (ref "J10") (pin "2") (pinfunction "2_2") (pintype "passive"))
      (node (ref "J2") (pin "7") (pinfunction "7_7") (pintype "passive"))
      (node (ref "J8") (pin "7") (pinfunction "7_7") (pintype "passive"))
    )
    (net (code "15") (name "BL_PWR_NEUTRAL_SIGNAL") (class "Default")
      (node (ref "A1") (pin "D64") (pinfunction "PK2_D64") (pintype "bidirectional"))
      (node (ref "R41") (pin "1") (pinfunction "1_1") (pintype "passive"))
      (node (ref "U23") (pin "4") (pinfunction "CO_4") (pintype "passive"))
    )
    (net (code "16") (name "BL_PWR_SIGNAL") (class "Default")
      (node (ref "A1") (pin "D58") (pinfunction "PF4_D58") (pintype "bidirectional"))
      (node (ref "R31") (pin "1") (pinfunction "1_1") (pintype "passive"))
      (node (ref "U15") (pin "4") (pinfunction "CO_4") (pintype "passive"))
    )
    (net (code "17") (name "BSKT_120_GND_SIGNAL") (class "Default")
      (node (ref "A1") (pin "D65") (pinfunction "PK3_D65") (pintype "bidirectional"))
      (node (ref "R44") (pin "1") (pinfunction "1_1") (pintype "passive"))
      (node (ref "U24") (pin "4") (pinfunction "CO_4") (pintype "passive"))
    )
    (net (code "18") (name "BSKT_CTRL") (class "Default")
      (node (ref "A1") (pin "D13") (pinfunction "PB7_D13") (pintype "bidirectional"))
      (node (ref "U14") (pin "1") (pinfunction "B_1") (pintype "passive"))
      (node (ref "U6") (pin "1") (pinfunction "B_1") (pintype "passive"))
    )
    (net (code "19") (name "BSKT_P1") (class "Default")
      (node (ref "J5") (pin "1") (pinfunction "1_1") (pintype "passive"))
      (node (ref "R11") (pin "1") (pinfunction "1_1") (pintype "passive"))
      (node (ref "R4") (pin "1") (pinfunction "1_1") (pintype "passive"))
    )
    (net (code "20") (name "BSKT_P2") (class "Default")
      (node (ref "J5") (pin "2") (pinfunction "2_2") (pintype "passive"))
      (node (ref "R36") (pin "1") (pinfunction "1_1") (pintype "passive"))
    )
    (net (code "21") (name "BSKT_P3") (class "Default")
      (node (ref "J5") (pin "3") (pinfunction "3_3") (pintype "passive"))
      (node (ref "U4") (pin "1") (pinfunction "A/C_1") (pintype "passive"))
    )
    (net (code "22") (name "BSKT_P4") (class "Default")
      (node (ref "J5") (pin "4") (pinfunction "4_4") (pintype "passive"))
      (node (ref "U24") (pin "1") (pinfunction "A/C_1") (pintype "passive"))
    )
    (net (code "23") (name "BSKT_P5") (class "Default")
      (node (ref "J5") (pin "5") (pinfunction "5_5") (pintype "passive"))
      (node (ref "U20") (pin "4") (pinfunction "D2_4") (pintype "bidirectional"))
      (node (ref "U8") (pin "4") (pinfunction "D2_4") (pintype "bidirectional"))
    )
    (net (code "24") (name "BSKT_P6") (class "Default")
      (node (ref "J5") (pin "6") (pinfunction "6_6") (pintype "passive"))
      (node (ref "U12") (pin "1") (pinfunction "A/C_1") (pintype "passive"))
    )
    (net (code "25") (name "EX1") (class "Default")
      (node (ref "A1") (pin "D66") (pinfunction "PK4_D66") (pintype "bidirectional"))
      (node (ref "J8") (pin "6") (pinfunction "6_6") (pintype "passive"))
    )
    (net (code "26") (name "EX2") (class "Default")
      (node (ref "A1") (pin "D67") (pinfunction "PK5_D67") (pintype "bidirectional"))
      (node (ref "J8") (pin "5") (pinfunction "5_5") (pintype "passive"))
    )
    (net (code "27") (name "EX3") (class "Default")
      (node (ref "A1") (pin "D68") (pinfunction "PK6_D68") (pintype "bidirectional"))
      (node (ref "J8") (pin "4") (pinfunction "4_4") (pintype "passive"))
    )
    (net (code "28") (name "GAS_VALVE_SIGNAL") (class "Default")
      (node (ref "A1") (pin "D62") (pinfunction "PK0_D62") (pintype "bidirectional"))
      (node (ref "R34") (pin "1") (pinfunction "1_1") (pintype "passive"))
      (node (ref "U18") (pin "4") (pinfunction "CO_4") (pintype "passive"))
    )
    (net (code "29") (name "GND") (class "Default")
      (node (ref "A1") (pin "GND") (pinfunction "GND_GND") (pintype "bidirectional"))
      (node (ref "A1") (pin "GND-2") (pinfunction "GND2_GND-2") (pintype "bidirectional"))
      (node (ref "A1") (pin "GND-3") (pinfunction "GND3_GND-3") (pintype "bidirectional"))
      (node (ref "A2") (pin "14") (pinfunction "GND_14") (pintype "bidirectional"))
      (node (ref "J10") (pin "7") (pinfunction "7_7") (pintype "passive"))
      (node (ref "J11") (pin "1") (pinfunction "1_1") (pintype "passive"))
      (node (ref "J7") (pin "P$2") (pinfunction "2_P$2") (pintype "passive"))
      (node (ref "J7") (pin "P$3") (pinfunction "3_P$3") (pintype "passive"))
      (node (ref "J8") (pin "3") (pinfunction "3_3") (pintype "passive"))
      (node (ref "J9") (pin "4") (pinfunction "4_4") (pintype "passive"))
      (node (ref "K1") (pin "L2") (pinfunction "5_L2") (pintype "bidirectional"))
      (node (ref "R12") (pin "1") (pinfunction "1_1") (pintype "passive"))
      (node (ref "R13") (pin "1") (pinfunction "1_1") (pintype "passive"))
      (node (ref "R29") (pin "1") (pinfunction "1_1") (pintype "passive"))
      (node (ref "R30") (pin "1") (pinfunction "1_1") (pintype "passive"))
      (node (ref "R42") (pin "1") (pinfunction "1_1") (pintype "passive"))
      (node (ref "R43") (pin "2") (pinfunction "2_2") (pintype "passive"))
      (node (ref "U1") (pin "GND") (pinfunction "GND_GND") (pintype "bidirectional"))
      (node (ref "U10") (pin "3") (pinfunction "E_3") (pintype "passive"))
      (node (ref "U11") (pin "3") (pinfunction "E_3") (pintype "passive"))
      (node (ref "U12") (pin "3") (pinfunction "E_3") (pintype "passive"))
      (node (ref "U15") (pin "3") (pinfunction "E_3") (pintype "passive"))
      (node (ref "U16") (pin "3") (pinfunction "E_3") (pintype "passive"))
      (node (ref "U17") (pin "3") (pinfunction "E_3") (pintype "passive"))
      (node (ref "U18") (pin "3") (pinfunction "E_3") (pintype "passive"))
      (node (ref "U2") (pin "GND") (pinfunction "GND_GND") (pintype "bidirectional"))
      (node (ref "U23") (pin "3") (pinfunction "E_3") (pintype "passive"))
      (node (ref "U24") (pin "3") (pinfunction "E_3") (pintype "passive"))
      (node (ref "U29") (pin "3") (pinfunction "E_3") (pintype "passive"))
      (node (ref "U3") (pin "3") (pinfunction "E_3") (pintype "passive"))
      (node (ref "U30") (pin "3") (pinfunction "E_3") (pintype "passive"))
      (node (ref "U4") (pin "3") (pinfunction "E_3") (pintype "passive"))
      (node (ref "U5") (pin "3") (pinfunction "E_3") (pintype "passive"))
    )
    (net (code "30") (name "INT") (class "Default")
      (node (ref "A1") (pin "D23") (pinfunction "D23_D23") (pintype "bidirectional"))
      (node (ref "A2") (pin "5") (pinfunction "INT_5") (pintype "bidirectional"))
    )
    (net (code "31") (name "JUMPER") (class "Default")
      (node (ref "J4") (pin "12") (pinfunction "12_12") (pintype "passive"))
      (node (ref "J4") (pin "8") (pinfunction "8_8") (pintype "passive"))
    )
    (net (code "32") (name "L_BSKT_SIGNAL") (class "Default")
      (node (ref "A1") (pin "D56") (pinfunction "PF2_D56") (pintype "bidirectional"))
      (node (ref "R16") (pin "1") (pinfunction "1_1") (pintype "passive"))
      (node (ref "U12") (pin "4") (pinfunction "CO_4") (pintype "passive"))
    )
    (net (code "33") (name "MISO") (class "Default")
      (node (ref "A1") (pin "D50") (pinfunction "D50_D50") (pintype "bidirectional"))
      (node (ref "A2") (pin "10") (pinfunction "MISO_10") (pintype "bidirectional"))
    )
    (net (code "34") (name "MOSI") (class "Default")
      (node (ref "A1") (pin "D51") (pinfunction "D51_D51") (pintype "bidirectional"))
      (node (ref "A2") (pin "9") (pinfunction "MOSI_9") (pintype "bidirectional"))
    )
    (net (code "35") (name "MP_P1") (class "Default")
      (node (ref "J4") (pin "1") (pinfunction "1_1") (pintype "passive"))
      (node (ref "U8") (pin "3") (pinfunction "D1_3") (pintype "bidirectional"))
    )
    (net (code "36") (name "MP_P2") (class "Default")
      (node (ref "J4") (pin "2") (pinfunction "2_2") (pintype "passive"))
      (node (ref "U20") (pin "3") (pinfunction "D1_3") (pintype "bidirectional"))
    )
    (net (code "37") (name "MP_P3") (class "Default")
      (node (ref "J10") (pin "3") (pinfunction "3_3") (pintype "passive"))
      (node (ref "J10") (pin "4") (pinfunction "4_4") (pintype "passive"))
      (node (ref "J10") (pin "5") (pinfunction "5_5") (pintype "passive"))
      (node (ref "J10") (pin "6") (pinfunction "6_6") (pintype "passive"))
      (node (ref "J4") (pin "3") (pinfunction "3_3") (pintype "passive"))
    )
    (net (code "38") (name "MP_P4") (class "Default")
      (node (ref "J4") (pin "4") (pinfunction "4_4") (pintype "passive"))
      (node (ref "U10") (pin "1") (pinfunction "A/C_1") (pintype "passive"))
      (node (ref "U19") (pin "4") (pinfunction "D2_4") (pintype "bidirectional"))
      (node (ref "U9") (pin "4") (pinfunction "D2_4") (pintype "bidirectional"))
    )
    (net (code "39") (name "MP_P5") (class "Default")
      (node (ref "J4") (pin "5") (pinfunction "5_5") (pintype "passive"))
      (node (ref "U18") (pin "1") (pinfunction "A/C_1") (pintype "passive"))
    )
    (net (code "40") (name "MP_P6") (class "Default")
      (node (ref "J4") (pin "6") (pinfunction "6_6") (pintype "passive"))
      (node (ref "U5") (pin "1") (pinfunction "A/C_1") (pintype "passive"))
    )
    (net (code "41") (name "MP_P7") (class "Default")
      (node (ref "J4") (pin "7") (pinfunction "7_7") (pintype "passive"))
      (node (ref "U9") (pin "3") (pinfunction "D1_3") (pintype "bidirectional"))
    )
    (net (code "42") (name "MP_P9") (class "Default")
      (node (ref "J4") (pin "9") (pinfunction "9_9") (pintype "passive"))
      (node (ref "U11") (pin "1") (pinfunction "A/C_1") (pintype "passive"))
      (node (ref "U19") (pin "3") (pinfunction "D1_3") (pintype "bidirectional"))
    )
    (net (code "43") (name "MP_P10") (class "Default")
      (node (ref "J4") (pin "10") (pinfunction "10_10") (pintype "passive"))
      (node (ref "K1") (pin "NO") (pinfunction "1_NO") (pintype "bidirectional"))
      (node (ref "R10") (pin "1") (pinfunction "1_1") (pintype "passive"))
      (node (ref "R20") (pin "1") (pinfunction "1_1") (pintype "passive"))
      (node (ref "R5") (pin "1") (pinfunction "1_1") (pintype "passive"))
      (node (ref "R9") (pin "1") (pinfunction "1_1") (pintype "passive"))
    )
    (net (code "44") (name "MP_P11") (class "Default")
      (node (ref "J4") (pin "11") (pinfunction "11_11") (pintype "passive"))
      (node (ref "K1") (pin "C") (pinfunction "3_C") (pintype "bidirectional"))
    )
    (net (code "45") (name "Net-(A1-PK7)") (class "Default")
      (node (ref "A1") (pin "D69") (pinfunction "PK7_D69") (pintype "bidirectional"))
      (node (ref "R1") (pin "2") (pinfunction "2_2") (pintype "passive"))
    )
    (net (code "46") (name "Net-(D1-ANODE)") (class "Default")
      (node (ref "D1") (pin "1") (pinfunction "ANODE_1") (pintype "bidirectional"))
      (node (ref "U27") (pin "1") (pinfunction "B_1") (pintype "passive"))
    )
    (net (code "47") (name "Net-(D1-CATHODE)") (class "Default")
      (node (ref "C1") (pin "1") (pinfunction "1_1") (pintype "passive"))
      (node (ref "D1") (pin "3") (pinfunction "CATHODE_3") (pintype "bidirectional"))
      (node (ref "R45") (pin "2") (pinfunction "2_2") (pintype "passive"))
    )
    (net (code "48") (name "Net-(D2-ANODE)") (class "Default")
      (node (ref "D2") (pin "1") (pinfunction "ANODE_1") (pintype "bidirectional"))
      (node (ref "U28") (pin "1") (pinfunction "B_1") (pintype "passive"))
    )
    (net (code "49") (name "Net-(D2-CATHODE)") (class "Default")
      (node (ref "C2") (pin "1") (pinfunction "1_1") (pintype "passive"))
      (node (ref "D2") (pin "3") (pinfunction "CATHODE_3") (pintype "bidirectional"))
      (node (ref "R46") (pin "2") (pinfunction "2_2") (pintype "passive"))
    )
    (net (code "50") (name "Net-(K1-4)") (class "Default")
      (node (ref "K1") (pin "L1") (pinfunction "4_L1") (pintype "bidirectional"))
      (node (ref "U25") (pin "3") (pinfunction "D1_3") (pintype "bidirectional"))
    )
    (net (code "51") (name "Net-(R17-Pad2)") (class "Default")
      (node (ref "R17") (pin "2") (pinfunction "2_2") (pintype "passive"))
      (node (ref "R21") (pin "1") (pinfunction "1_1") (pintype "passive"))
    )
    (net (code "52") (name "Net-(R18-Pad2)") (class "Default")
      (node (ref "R18") (pin "2") (pinfunction "2_2") (pintype "passive"))
      (node (ref "R22") (pin "1") (pinfunction "1_1") (pintype "passive"))
    )
    (net (code "53") (name "Net-(R19-Pad2)") (class "Default")
      (node (ref "R19") (pin "2") (pinfunction "2_2") (pintype "passive"))
      (node (ref "R23") (pin "1") (pinfunction "1_1") (pintype "passive"))
    )
    (net (code "54") (name "Net-(R20-Pad2)") (class "Default")
      (node (ref "R20") (pin "2") (pinfunction "2_2") (pintype "passive"))
      (node (ref "R24") (pin "1") (pinfunction "1_1") (pintype "passive"))
    )
    (net (code "55") (name "Net-(R21-Pad2)") (class "Default")
      (node (ref "R21") (pin "2") (pinfunction "2_2") (pintype "passive"))
      (node (ref "R25") (pin "1") (pinfunction "1_1") (pintype "passive"))
    )
    (net (code "56") (name "Net-(R22-Pad2)") (class "Default")
      (node (ref "R22") (pin "2") (pinfunction "2_2") (pintype "passive"))
      (node (ref "R26") (pin "1") (pinfunction "1_1") (pintype "passive"))
    )
    (net (code "57") (name "Net-(R23-Pad2)") (class "Default")
      (node (ref "R23") (pin "2") (pinfunction "2_2") (pintype "passive"))
      (node (ref "R27") (pin "1") (pinfunction "1_1") (pintype "passive"))
    )
    (net (code "58") (name "Net-(R24-Pad2)") (class "Default")
      (node (ref "R24") (pin "2") (pinfunction "2_2") (pintype "passive"))
      (node (ref "R28") (pin "1") (pinfunction "1_1") (pintype "passive"))
    )
    (net (code "59") (name "Net-(R35-Pad2)") (class "Default")
      (node (ref "R35") (pin "2") (pinfunction "2_2") (pintype "passive"))
      (node (ref "R37") (pin "1") (pinfunction "1_1") (pintype "passive"))
    )
    (net (code "60") (name "Net-(R36-Pad2)") (class "Default")
      (node (ref "R36") (pin "2") (pinfunction "2_2") (pintype "passive"))
      (node (ref "R38") (pin "1") (pinfunction "1_1") (pintype "passive"))
    )
    (net (code "61") (name "Net-(R37-Pad2)") (class "Default")
      (node (ref "R37") (pin "2") (pinfunction "2_2") (pintype "passive"))
      (node (ref "R39") (pin "1") (pinfunction "1_1") (pintype "passive"))
    )
    (net (code "62") (name "Net-(R38-Pad2)") (class "Default")
      (node (ref "R38") (pin "2") (pinfunction "2_2") (pintype "passive"))
      (node (ref "R40") (pin "1") (pinfunction "1_1") (pintype "passive"))
    )
    (net (code "63") (name "Net-(R47-Pad1)") (class "Default")
      (node (ref "R47") (pin "1") (pinfunction "1_1") (pintype "passive"))
      (node (ref "U27") (pin "2") (pinfunction "C_2") (pintype "passive"))
      (node (ref "U27") (pin "4") (pinfunction "C_4") (pintype "passive"))
    )
    (net (code "64") (name "Net-(R48-Pad1)") (class "Default")
      (node (ref "R48") (pin "1") (pinfunction "1_1") (pintype "passive"))
      (node (ref "U28") (pin "2") (pinfunction "C_2") (pintype "passive"))
      (node (ref "U28") (pin "4") (pinfunction "C_4") (pintype "passive"))
    )
    (net (code "65") (name "Net-(U3-C{slash}A)") (class "Default")
      (node (ref "R3") (pin "2") (pinfunction "2_2") (pintype "passive"))
      (node (ref "U3") (pin "2") (pinfunction "C/A_2") (pintype "passive"))
    )
    (net (code "66") (name "Net-(U4-C{slash}A)") (class "Default")
      (node (ref "R4") (pin "2") (pinfunction "2_2") (pintype "passive"))
      (node (ref "U4") (pin "2") (pinfunction "C/A_2") (pintype "passive"))
    )
    (net (code "67") (name "Net-(U5-C{slash}A)") (class "Default")
      (node (ref "R5") (pin "2") (pinfunction "2_2") (pintype "passive"))
      (node (ref "U5") (pin "2") (pinfunction "C/A_2") (pintype "passive"))
    )
    (net (code "68") (name "Net-(U6-E)") (class "Default")
      (node (ref "U6") (pin "3") (pinfunction "E_3") (pintype "passive"))
      (node (ref "U8") (pin "1") (pinfunction "A_1") (pintype "bidirectional"))
    )
    (net (code "69") (name "Net-(U7-E)") (class "Default")
      (node (ref "U7") (pin "3") (pinfunction "E_3") (pintype "passive"))
      (node (ref "U9") (pin "1") (pinfunction "A_1") (pintype "bidirectional"))
    )
    (net (code "70") (name "Net-(U8-K)") (class "Default")
      (node (ref "R12") (pin "2") (pinfunction "2_2") (pintype "passive"))
      (node (ref "U8") (pin "2") (pinfunction "K_2") (pintype "bidirectional"))
    )
    (net (code "71") (name "Net-(U9-K)") (class "Default")
      (node (ref "R13") (pin "2") (pinfunction "2_2") (pintype "passive"))
      (node (ref "U9") (pin "2") (pinfunction "K_2") (pintype "bidirectional"))
    )
    (net (code "72") (name "Net-(U10-C{slash}A)") (class "Default")
      (node (ref "R9") (pin "2") (pinfunction "2_2") (pintype "passive"))
      (node (ref "U10") (pin "2") (pinfunction "C/A_2") (pintype "passive"))
    )
    (net (code "73") (name "Net-(U11-C{slash}A)") (class "Default")
      (node (ref "R10") (pin "2") (pinfunction "2_2") (pintype "passive"))
      (node (ref "U11") (pin "2") (pinfunction "C/A_2") (pintype "passive"))
    )
    (net (code "74") (name "Net-(U12-C{slash}A)") (class "Default")
      (node (ref "R11") (pin "2") (pinfunction "2_2") (pintype "passive"))
      (node (ref "U12") (pin "2") (pinfunction "C/A_2") (pintype "passive"))
    )
    (net (code "75") (name "Net-(U13-E)") (class "Default")
      (node (ref "U13") (pin "3") (pinfunction "E_3") (pintype "passive"))
      (node (ref "U19") (pin "1") (pinfunction "A_1") (pintype "bidirectional"))
    )
    (net (code "76") (name "Net-(U14-E)") (class "Default")
      (node (ref "U14") (pin "3") (pinfunction "E_3") (pintype "passive"))
      (node (ref "U20") (pin "1") (pinfunction "A_1") (pintype "bidirectional"))
    )
    (net (code "77") (name "Net-(U15-C{slash}A)") (class "Default")
      (node (ref "R25") (pin "2") (pinfunction "2_2") (pintype "passive"))
      (node (ref "U15") (pin "2") (pinfunction "C/A_2") (pintype "passive"))
    )
    (net (code "78") (name "Net-(U16-C{slash}A)") (class "Default")
      (node (ref "R26") (pin "2") (pinfunction "2_2") (pintype "passive"))
      (node (ref "U16") (pin "2") (pinfunction "C/A_2") (pintype "passive"))
    )
    (net (code "79") (name "Net-(U17-C{slash}A)") (class "Default")
      (node (ref "R27") (pin "2") (pinfunction "2_2") (pintype "passive"))
      (node (ref "U17") (pin "2") (pinfunction "C/A_2") (pintype "passive"))
    )
    (net (code "80") (name "Net-(U18-C{slash}A)") (class "Default")
      (node (ref "R28") (pin "2") (pinfunction "2_2") (pintype "passive"))
      (node (ref "U18") (pin "2") (pinfunction "C/A_2") (pintype "passive"))
    )
    (net (code "81") (name "Net-(U19-K)") (class "Default")
      (node (ref "R29") (pin "2") (pinfunction "2_2") (pintype "passive"))
      (node (ref "U19") (pin "2") (pinfunction "K_2") (pintype "bidirectional"))
    )
    (net (code "82") (name "Net-(U20-K)") (class "Default")
      (node (ref "R30") (pin "2") (pinfunction "2_2") (pintype "passive"))
      (node (ref "U20") (pin "2") (pinfunction "K_2") (pintype "bidirectional"))
    )
    (net (code "83") (name "Net-(U21-E)") (class "Default")
      (node (ref "U21") (pin "3") (pinfunction "E_3") (pintype "passive"))
      (node (ref "U25") (pin "1") (pinfunction "A_1") (pintype "bidirectional"))
    )
    (net (code "84") (name "Net-(U22-E)") (class "Default")
      (node (ref "U22") (pin "3") (pinfunction "E_3") (pintype "passive"))
      (node (ref "U26") (pin "1") (pinfunction "A_1") (pintype "bidirectional"))
    )
    (net (code "85") (name "Net-(U23-C{slash}A)") (class "Default")
      (node (ref "R39") (pin "2") (pinfunction "2_2") (pintype "passive"))
      (node (ref "U23") (pin "2") (pinfunction "C/A_2") (pintype "passive"))
    )
    (net (code "86") (name "Net-(U24-C{slash}A)") (class "Default")
      (node (ref "R40") (pin "2") (pinfunction "2_2") (pintype "passive"))
      (node (ref "U24") (pin "2") (pinfunction "C/A_2") (pintype "passive"))
    )
    (net (code "87") (name "Net-(U25-K)") (class "Default")
      (node (ref "R43") (pin "1") (pinfunction "1_1") (pintype "passive"))
      (node (ref "U25") (pin "2") (pinfunction "K_2") (pintype "bidirectional"))
    )
    (net (code "88") (name "Net-(U26-K)") (class "Default")
      (node (ref "R42") (pin "2") (pinfunction "2_2") (pintype "passive"))
      (node (ref "U26") (pin "2") (pinfunction "K_2") (pintype "bidirectional"))
    )
    (net (code "89") (name "Net-(U27-E)") (class "Default")
      (node (ref "U27") (pin "3") (pinfunction "E_3") (pintype "passive"))
      (node (ref "U30") (pin "1") (pinfunction "A/C_1") (pintype "passive"))
    )
    (net (code "90") (name "Net-(U28-E)") (class "Default")
      (node (ref "U28") (pin "3") (pinfunction "E_3") (pintype "passive"))
      (node (ref "U29") (pin "1") (pinfunction "A/C_1") (pintype "passive"))
    )
    (net (code "91") (name "PM_P1") (class "Default")
      (node (ref "J3") (pin "1") (pinfunction "1_1") (pintype "passive"))
      (node (ref "U17") (pin "1") (pinfunction "A/C_1") (pintype "passive"))
    )
    (net (code "92") (name "PM_P2") (class "Default")
      (node (ref "J3") (pin "2") (pinfunction "2_2") (pintype "passive"))
      (node (ref "R19") (pin "1") (pinfunction "1_1") (pintype "passive"))
    )
    (net (code "93") (name "PM_PWR_SIGNAL") (class "Default")
      (node (ref "A1") (pin "D60") (pinfunction "PF6_D60") (pintype "bidirectional"))
      (node (ref "R33") (pin "1") (pinfunction "1_1") (pintype "passive"))
      (node (ref "U17") (pin "4") (pinfunction "CO_4") (pintype "passive"))
    )
    (net (code "94") (name "PON_SIGNAL") (class "Default")
      (node (ref "A1") (pin "D61") (pinfunction "PF7_D61") (pintype "bidirectional"))
      (node (ref "R14") (pin "1") (pinfunction "1_1") (pintype "passive"))
      (node (ref "U10") (pin "4") (pinfunction "CO_4") (pintype "passive"))
    )
    (net (code "95") (name "POWER_CTRL") (class "Default")
      (node (ref "A1") (pin "D12") (pinfunction "PB6_D12") (pintype "bidirectional"))
      (node (ref "U21") (pin "1") (pinfunction "B_1") (pintype "passive"))
    )
    (net (code "96") (name "PUMP_CTRL") (class "Default")
      (node (ref "A1") (pin "D11") (pinfunction "PB5_D11") (pintype "bidirectional"))
      (node (ref "U7") (pin "1") (pinfunction "B_1") (pintype "passive"))
    )
    (net (code "97") (name "PWM_HIGH_SIGNAL") (class "Default")
      (node (ref "A1") (pin "D4") (pinfunction "PG5_D4") (pintype "bidirectional"))
      (node (ref "R50") (pin "1") (pinfunction "1_1") (pintype "passive"))
      (node (ref "U30") (pin "4") (pinfunction "CO_4") (pintype "passive"))
    )
    (net (code "98") (name "PWM_LOW_SIGNAL") (class "Default")
      (node (ref "A1") (pin "D5") (pinfunction "PE3_D5") (pintype "bidirectional"))
      (node (ref "R49") (pin "1") (pinfunction "1_1") (pintype "passive"))
      (node (ref "U29") (pin "4") (pinfunction "CO_4") (pintype "passive"))
    )
    (net (code "99") (name "RST") (class "Default")
      (node (ref "A1") (pin "D22") (pinfunction "D22_D22") (pintype "bidirectional"))
      (node (ref "A2") (pin "7") (pinfunction "RST_7") (pintype "bidirectional"))
    )
    (net (code "100") (name "R_BSKT_SIGNAL") (class "Default")
      (node (ref "A1") (pin "D55") (pinfunction "PF1_D55") (pintype "bidirectional"))
      (node (ref "R7") (pin "1") (pinfunction "1_1") (pintype "passive"))
      (node (ref "U4") (pin "4") (pinfunction "CO_4") (pintype "passive"))
    )
    (net (code "101") (name "SCK") (class "Default")
      (node (ref "A1") (pin "D52") (pinfunction "D52_D52") (pintype "bidirectional"))
      (node (ref "A2") (pin "11") (pinfunction "SCK_11") (pintype "bidirectional"))
    )
    (net (code "102") (name "SP_A1") (class "Default")
      (node (ref "A1") (pin "D54") (pinfunction "PF0_D54") (pintype "bidirectional"))
      (node (ref "J11") (pin "2") (pinfunction "2_2") (pintype "passive"))
      (node (ref "J9") (pin "1") (pinfunction "1_1") (pintype "passive"))
    )
    (net (code "103") (name "SP_D1") (class "Default")
      (node (ref "A1") (pin "D7") (pinfunction "PH4_D7") (pintype "bidirectional"))
      (node (ref "J9") (pin "6") (pinfunction "6_6") (pintype "passive"))
    )
    (net (code "104") (name "SP_D2") (class "Default")
      (node (ref "A1") (pin "D6") (pinfunction "PH3_D6") (pintype "bidirectional"))
      (node (ref "J9") (pin "5") (pinfunction "5_5") (pintype "passive"))
    )
    (net (code "105") (name "SVR_P1") (class "Default")
      (node (ref "J1") (pin "1") (pinfunction "1_1") (pintype "passive"))
      (node (ref "U26") (pin "3") (pinfunction "D1_3") (pintype "bidirectional"))
    )
    (net (code "106") (name "SVR_P3") (class "Default")
      (node (ref "J1") (pin "3") (pinfunction "3_3") (pintype "passive"))
      (node (ref "U26") (pin "4") (pinfunction "D2_4") (pintype "bidirectional"))
    )
    (net (code "107") (name "SV_P1") (class "Default")
      (node (ref "J6") (pin "1") (pinfunction "1_1") (pintype "passive"))
      (node (ref "R18") (pin "1") (pinfunction "1_1") (pintype "passive"))
    )
    (net (code "108") (name "SV_P4") (class "Default")
      (node (ref "J6") (pin "4") (pinfunction "4_4") (pintype "passive"))
      (node (ref "U16") (pin "1") (pinfunction "A/C_1") (pintype "passive"))
    )
    (net (code "109") (name "S_VALVE_CTRL") (class "Default")
      (node (ref "A1") (pin "D9") (pinfunction "PH6_D9") (pintype "bidirectional"))
      (node (ref "U22") (pin "1") (pinfunction "B_1") (pintype "passive"))
    )
    (net (code "110") (name "S_VALVE_SIGNAL") (class "Default")
      (node (ref "A1") (pin "D59") (pinfunction "PF5_D59") (pintype "bidirectional"))
      (node (ref "R32") (pin "1") (pinfunction "1_1") (pintype "passive"))
      (node (ref "U16") (pin "4") (pinfunction "CO_4") (pintype "passive"))
    )
    (net (code "111") (name "TH_CALL_CTRL") (class "Default")
      (node (ref "A1") (pin "D10") (pinfunction "PB4_D10") (pintype "bidirectional"))
      (node (ref "U13") (pin "1") (pinfunction "B_1") (pintype "passive"))
    )
    (net (code "112") (name "TH_CALL_SIGNAL") (class "Default")
      (node (ref "R15") (pin "1") (pinfunction "1_1") (pintype "passive"))
      (node (ref "U11") (pin "4") (pinfunction "CO_4") (pintype "passive"))
    )
    (net (code "113") (name "unconnected-(A1-+5V_2-Pad+5V-2)") (class "Default")
      (node (ref "A1") (pin "+5V-2") (pinfunction "+5V_2_+5V-2") (pintype "bidirectional"))
    )
    (net (code "114") (name "unconnected-(A1-+5V_3-Pad+5V-3)") (class "Default")
      (node (ref "A1") (pin "+5V-3") (pinfunction "+5V_3_+5V-3") (pintype "bidirectional"))
    )
    (net (code "115") (name "unconnected-(A1-GND4-PadGND-4)") (class "Default")
      (node (ref "A1") (pin "GND-4") (pinfunction "GND4_GND-4") (pintype "bidirectional"))
    )
    (net (code "116") (name "unconnected-(A1-GND5-PadGND-5)") (class "Default")
      (node (ref "A1") (pin "GND-5") (pinfunction "GND5_GND-5") (pintype "bidirectional"))
    )
    (net (code "117") (name "unconnected-(A1-PD0-2-PadD21-2)") (class "Default")
      (node (ref "A1") (pin "D21-2") (pinfunction "PD0-2_D21-2") (pintype "bidirectional"))
    )
    (net (code "118") (name "unconnected-(A1-PD0-PadD21)") (class "Default")
      (node (ref "A1") (pin "D21") (pinfunction "PD0_D21") (pintype "bidirectional"))
    )
    (net (code "119") (name "unconnected-(A1-PD1-2-PadD20-2)") (class "Default")
      (node (ref "A1") (pin "D20-2") (pinfunction "PD1-2_D20-2") (pintype "bidirectional"))
    )
    (net (code "120") (name "unconnected-(A1-PD1-PadD20)") (class "Default")
      (node (ref "A1") (pin "D20") (pinfunction "PD1_D20") (pintype "bidirectional"))
    )
    (net (code "121") (name "unconnected-(A1-PD2-PadD19)") (class "Default")
      (node (ref "A1") (pin "D19") (pinfunction "PD2_D19") (pintype "bidirectional"))
    )
    (net (code "122") (name "unconnected-(A1-PD3-PadD18)") (class "Default")
      (node (ref "A1") (pin "D18") (pinfunction "PD3_D18") (pintype "bidirectional"))
    )
    (net (code "123") (name "unconnected-(A1-PE0-PadD0)") (class "Default")
      (node (ref "A1") (pin "D0") (pinfunction "PE0_D0") (pintype "bidirectional"))
    )
    (net (code "124") (name "unconnected-(A1-PE1-PadD1)") (class "Default")
      (node (ref "A1") (pin "D1") (pinfunction "PE1_D1") (pintype "bidirectional"))
    )
    (net (code "125") (name "unconnected-(A1-PE4-PadD2)") (class "Default")
      (node (ref "A1") (pin "D2") (pinfunction "PE4_D2") (pintype "bidirectional"))
    )
    (net (code "126") (name "unconnected-(A1-PE5-PadD3)") (class "Default")
      (node (ref "A1") (pin "D3") (pinfunction "PE5_D3") (pintype "bidirectional"))
    )
    (net (code "127") (name "unconnected-(A1-PH0-PadD17)") (class "Default")
      (node (ref "A1") (pin "D17") (pinfunction "PH0_D17") (pintype "bidirectional"))
    )
    (net (code "128") (name "unconnected-(A1-PH1-PadD16)") (class "Default")
      (node (ref "A1") (pin "D16") (pinfunction "PH1_D16") (pintype "bidirectional"))
    )
    (net (code "129") (name "unconnected-(A1-PH5-PadD8)") (class "Default")
      (node (ref "A1") (pin "D8") (pinfunction "PH5_D8") (pintype "bidirectional"))
    )
    (net (code "130") (name "unconnected-(A1-PJ0-PadD15)") (class "Default")
      (node (ref "A1") (pin "D15") (pinfunction "PJ0_D15") (pintype "bidirectional"))
    )
    (net (code "131") (name "unconnected-(A1-PJ1-PadD14)") (class "Default")
      (node (ref "A1") (pin "D14") (pinfunction "PJ1_D14") (pintype "bidirectional"))
    )
    (net (code "132") (name "unconnected-(A1-Pad+3V3)") (class "Default")
      (node (ref "A1") (pin "+3V3") (pinfunction "+3V3_+3V3") (pintype "bidirectional"))
    )
    (net (code "133") (name "unconnected-(A1-Pad+5V)") (class "Default")
      (node (ref "A1") (pin "+5V") (pinfunction "+5V_+5V") (pintype "bidirectional"))
    )
    (net (code "134") (name "unconnected-(A1-PadAREF)") (class "Default")
      (node (ref "A1") (pin "AREF") (pinfunction "AREF_AREF") (pintype "bidirectional"))
    )
    (net (code "135") (name "unconnected-(A1-PadD24)") (class "Default")
      (node (ref "A1") (pin "D24") (pinfunction "D24_D24") (pintype "bidirectional"))
    )
    (net (code "136") (name "unconnected-(A1-PadD25)") (class "Default")
      (node (ref "A1") (pin "D25") (pinfunction "D25_D25") (pintype "bidirectional"))
    )
    (net (code "137") (name "unconnected-(A1-PadD26)") (class "Default")
      (node (ref "A1") (pin "D26") (pinfunction "D26_D26") (pintype "bidirectional"))
    )
    (net (code "138") (name "unconnected-(A1-PadD27)") (class "Default")
      (node (ref "A1") (pin "D27") (pinfunction "D27_D27") (pintype "bidirectional"))
    )
    (net (code "139") (name "unconnected-(A1-PadD28)") (class "Default")
      (node (ref "A1") (pin "D28") (pinfunction "D28_D28") (pintype "bidirectional"))
    )
    (net (code "140") (name "unconnected-(A1-PadD29)") (class "Default")
      (node (ref "A1") (pin "D29") (pinfunction "D29_D29") (pintype "bidirectional"))
    )
    (net (code "141") (name "unconnected-(A1-PadD30)") (class "Default")
      (node (ref "A1") (pin "D30") (pinfunction "D30_D30") (pintype "bidirectional"))
    )
    (net (code "142") (name "unconnected-(A1-PadD31)") (class "Default")
      (node (ref "A1") (pin "D31") (pinfunction "D31_D31") (pintype "bidirectional"))
    )
    (net (code "143") (name "unconnected-(A1-PadD32)") (class "Default")
      (node (ref "A1") (pin "D32") (pinfunction "D32_D32") (pintype "bidirectional"))
    )
    (net (code "144") (name "unconnected-(A1-PadD33)") (class "Default")
      (node (ref "A1") (pin "D33") (pinfunction "D33_D33") (pintype "bidirectional"))
    )
    (net (code "145") (name "unconnected-(A1-PadD34)") (class "Default")
      (node (ref "A1") (pin "D34") (pinfunction "D34_D34") (pintype "bidirectional"))
    )
    (net (code "146") (name "unconnected-(A1-PadD35)") (class "Default")
      (node (ref "A1") (pin "D35") (pinfunction "D35_D35") (pintype "bidirectional"))
    )
    (net (code "147") (name "unconnected-(A1-PadD36)") (class "Default")
      (node (ref "A1") (pin "D36") (pinfunction "D36_D36") (pintype "bidirectional"))
    )
    (net (code "148") (name "unconnected-(A1-PadD37)") (class "Default")
      (node (ref "A1") (pin "D37") (pinfunction "D37_D37") (pintype "bidirectional"))
    )
    (net (code "149") (name "unconnected-(A1-PadD38)") (class "Default")
      (node (ref "A1") (pin "D38") (pinfunction "D38_D38") (pintype "bidirectional"))
    )
    (net (code "150") (name "unconnected-(A1-PadD39)") (class "Default")
      (node (ref "A1") (pin "D39") (pinfunction "D39_D39") (pintype "bidirectional"))
    )
    (net (code "151") (name "unconnected-(A1-PadD40)") (class "Default")
      (node (ref "A1") (pin "D40") (pinfunction "D40_D40") (pintype "bidirectional"))
    )
    (net (code "152") (name "unconnected-(A1-PadD41)") (class "Default")
      (node (ref "A1") (pin "D41") (pinfunction "D41_D41") (pintype "bidirectional"))
    )
    (net (code "153") (name "unconnected-(A1-PadD42)") (class "Default")
      (node (ref "A1") (pin "D42") (pinfunction "D42_D42") (pintype "bidirectional"))
    )
    (net (code "154") (name "unconnected-(A1-PadD43)") (class "Default")
      (node (ref "A1") (pin "D43") (pinfunction "D43_D43") (pintype "bidirectional"))
    )
    (net (code "155") (name "unconnected-(A1-PadD44)") (class "Default")
      (node (ref "A1") (pin "D44") (pinfunction "D44_D44") (pintype "bidirectional"))
    )
    (net (code "156") (name "unconnected-(A1-PadD45)") (class "Default")
      (node (ref "A1") (pin "D45") (pinfunction "D45_D45") (pintype "bidirectional"))
    )
    (net (code "157") (name "unconnected-(A1-PadD46)") (class "Default")
      (node (ref "A1") (pin "D46") (pinfunction "D46_D46") (pintype "bidirectional"))
    )
    (net (code "158") (name "unconnected-(A1-PadD47)") (class "Default")
      (node (ref "A1") (pin "D47") (pinfunction "D47_D47") (pintype "bidirectional"))
    )
    (net (code "159") (name "unconnected-(A1-PadD48)") (class "Default")
      (node (ref "A1") (pin "D48") (pinfunction "D48_D48") (pintype "bidirectional"))
    )
    (net (code "160") (name "unconnected-(A1-PadD49)") (class "Default")
      (node (ref "A1") (pin "D49") (pinfunction "D49_D49") (pintype "bidirectional"))
    )
    (net (code "161") (name "unconnected-(A1-PadIOREF)") (class "Default")
      (node (ref "A1") (pin "IOREF") (pinfunction "IOREF_IOREF") (pintype "bidirectional"))
    )
    (net (code "162") (name "unconnected-(A1-PadNC)") (class "Default")
      (node (ref "A1") (pin "NC") (pinfunction "NC_NC") (pintype "bidirectional"))
    )
    (net (code "163") (name "unconnected-(A1-~{RESET}-Pad!RESET!)") (class "Default")
      (node (ref "A1") (pin "!RESET!") (pinfunction "~{RESET}_!RESET!") (pintype "bidirectional"))
    )
    (net (code "164") (name "unconnected-(A2-+3V3-Pad13)") (class "Default")
      (node (ref "A2") (pin "13") (pinfunction "+3V3_13") (pintype "bidirectional"))
    )
    (net (code "165") (name "unconnected-(A2-LITE-Pad12)") (class "Default")
      (node (ref "A2") (pin "12") (pinfunction "LITE_12") (pintype "bidirectional"))
    )
    (net (code "166") (name "unconnected-(A2-WAIT-Pad6)") (class "Default")
      (node (ref "A2") (pin "6") (pinfunction "WAIT_6") (pintype "bidirectional"))
    )
    (net (code "167") (name "unconnected-(A2-X+-Pad1)") (class "Default")
      (node (ref "A2") (pin "1") (pinfunction "X+_1") (pintype "bidirectional"))
    )
    (net (code "168") (name "unconnected-(A2-X--Pad2)") (class "Default")
      (node (ref "A2") (pin "2") (pinfunction "X-_2") (pintype "bidirectional"))
    )
    (net (code "169") (name "unconnected-(A2-Y+-Pad4)") (class "Default")
      (node (ref "A2") (pin "4") (pinfunction "Y+_4") (pintype "bidirectional"))
    )
    (net (code "170") (name "unconnected-(A2-Y--Pad3)") (class "Default")
      (node (ref "A2") (pin "3") (pinfunction "Y-_3") (pintype "bidirectional"))
    )
    (net (code "171") (name "unconnected-(D1-NOT_CONNECTED-Pad2)") (class "Default")
      (node (ref "D1") (pin "2") (pinfunction "NOT_CONNECTED_2") (pintype "bidirectional"))
    )
    (net (code "172") (name "unconnected-(D2-NOT_CONNECTED-Pad2)") (class "Default")
      (node (ref "D2") (pin "2") (pinfunction "NOT_CONNECTED_2") (pintype "bidirectional"))
    )
    (net (code "173") (name "unconnected-(J1-Pad2)") (class "Default")
      (node (ref "J1") (pin "2") (pinfunction "2_2") (pintype "passive"))
    )
    (net (code "174") (name "unconnected-(J2-Pad8)") (class "Default")
      (node (ref "J2") (pin "8") (pinfunction "8_8") (pintype "passive"))
    )
    (net (code "175") (name "unconnected-(J6-Pad2)") (class "Default")
      (node (ref "J6") (pin "2") (pinfunction "2_2") (pintype "passive"))
    )
    (net (code "176") (name "unconnected-(J6-Pad3)") (class "Default")
      (node (ref "J6") (pin "3") (pinfunction "3_3") (pintype "passive"))
    )
    (net (code "177") (name "unconnected-(K1-2-PadNC)") (class "Default")
      (node (ref "K1") (pin "NC") (pinfunction "2_NC") (pintype "bidirectional"))
    )
  )
)
